# 03_-_28PINS_SCHEMATIC.net
KiCad netlist of a schematic drawn in Altium Designer
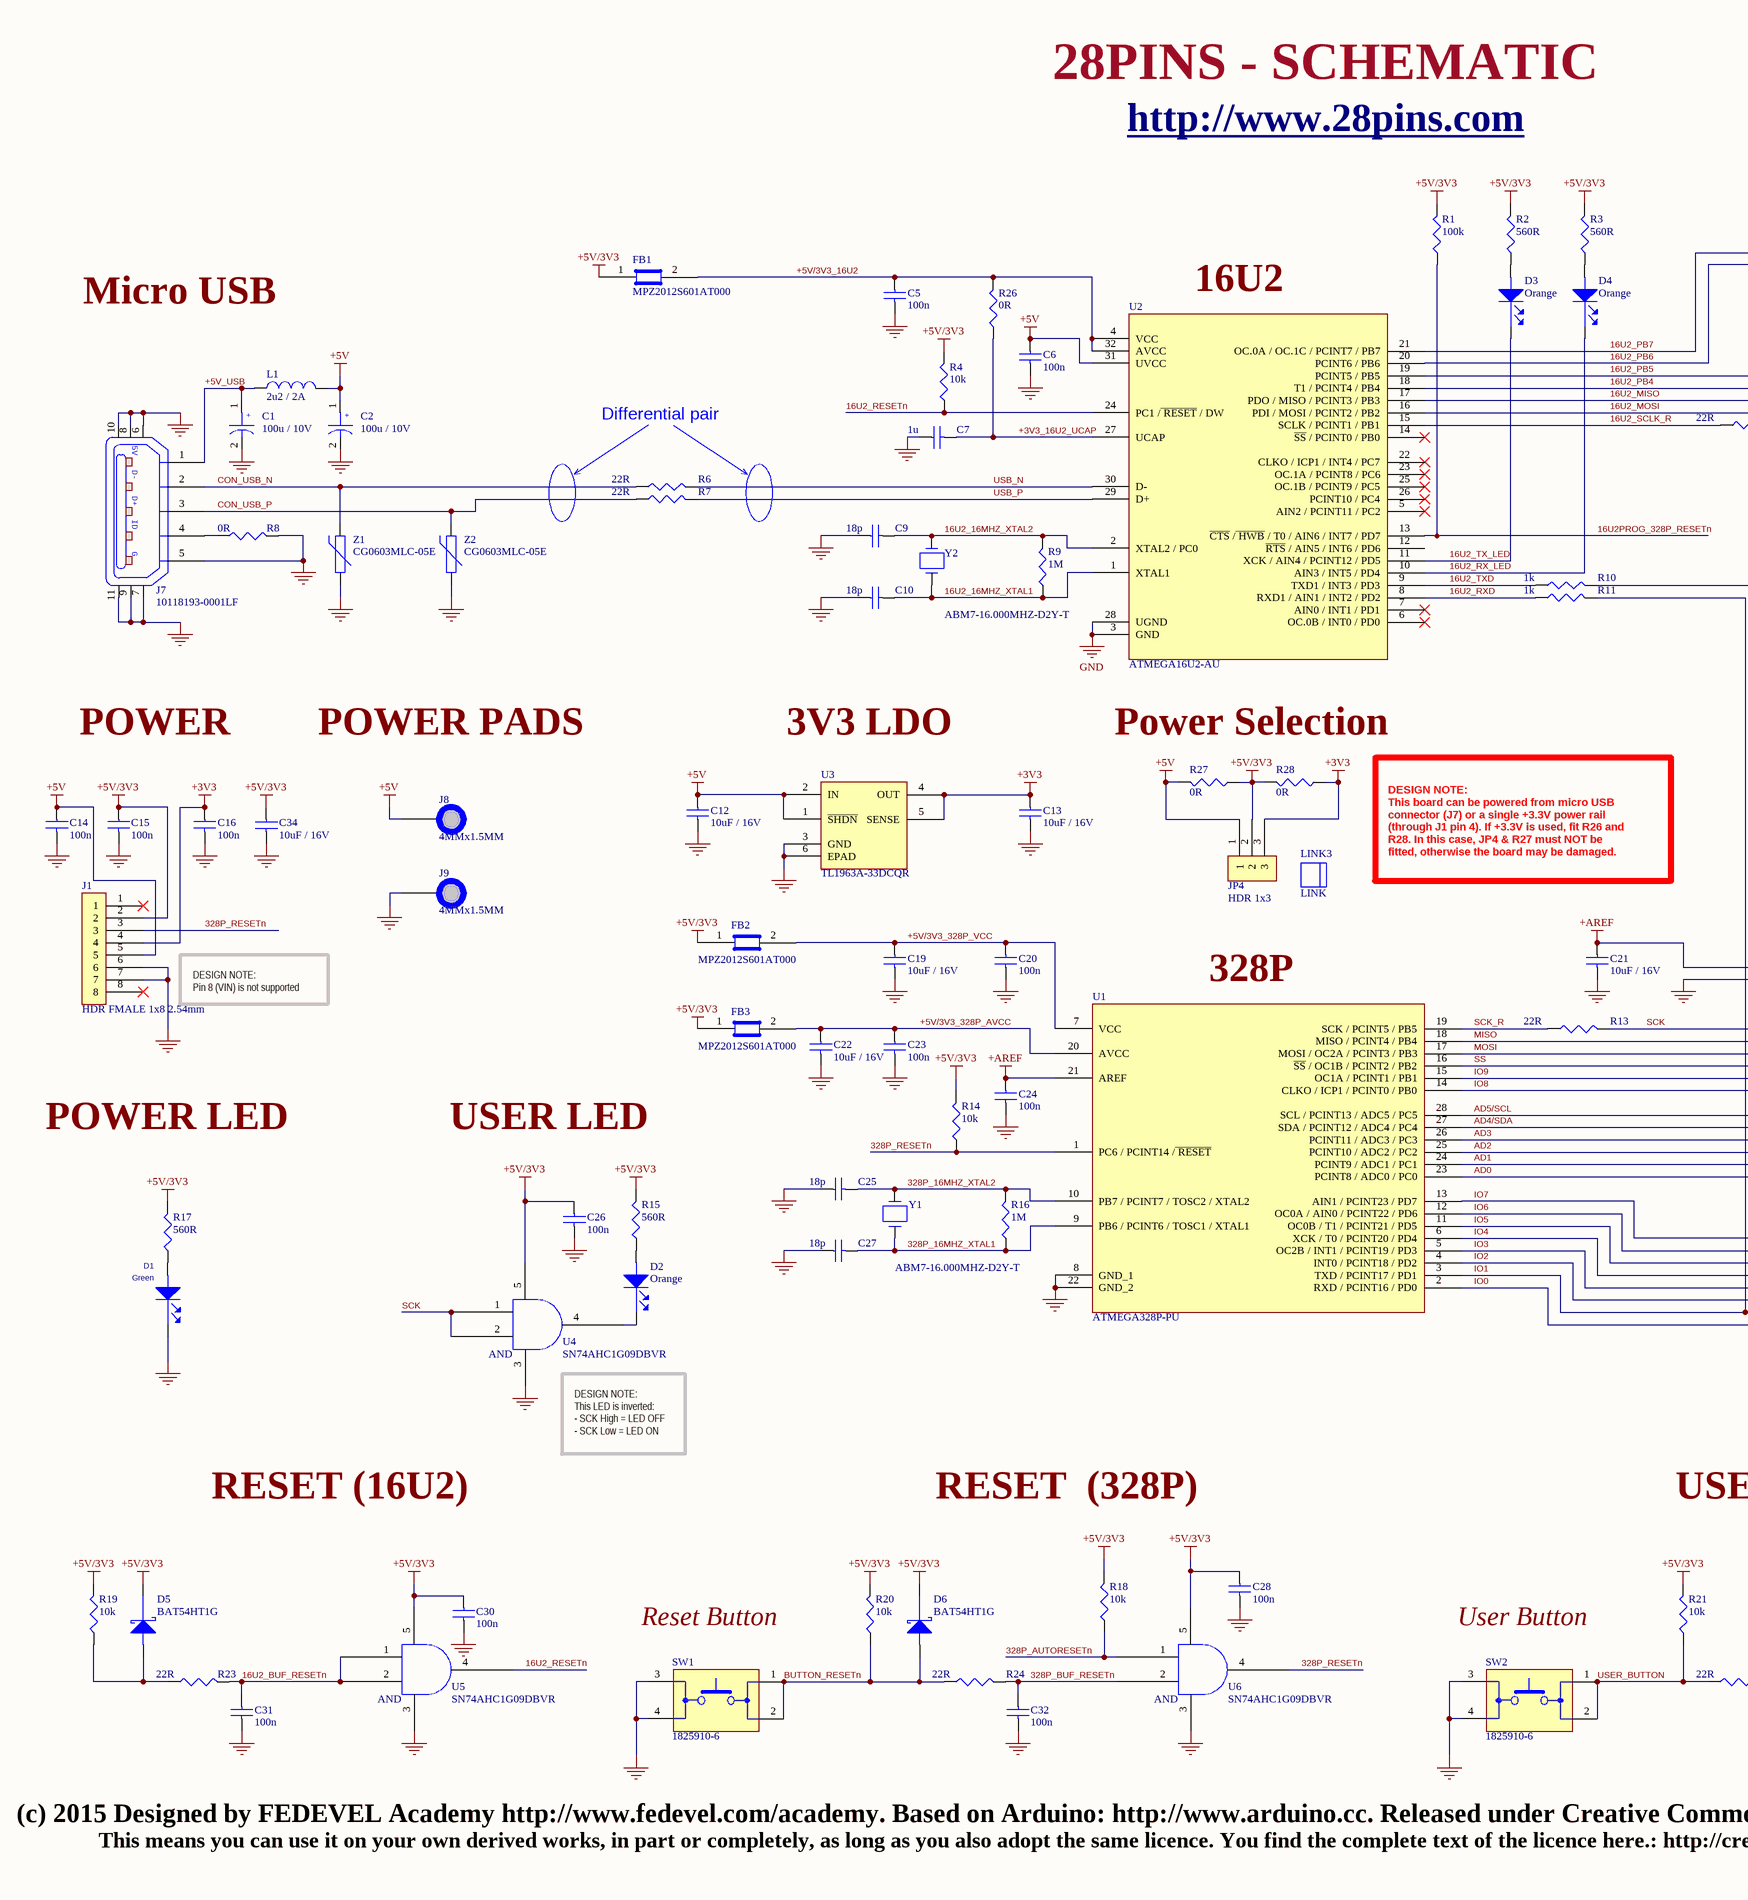
[diagram p0: [03] - 28PINS SCHEMATIC.SchDoc, left]
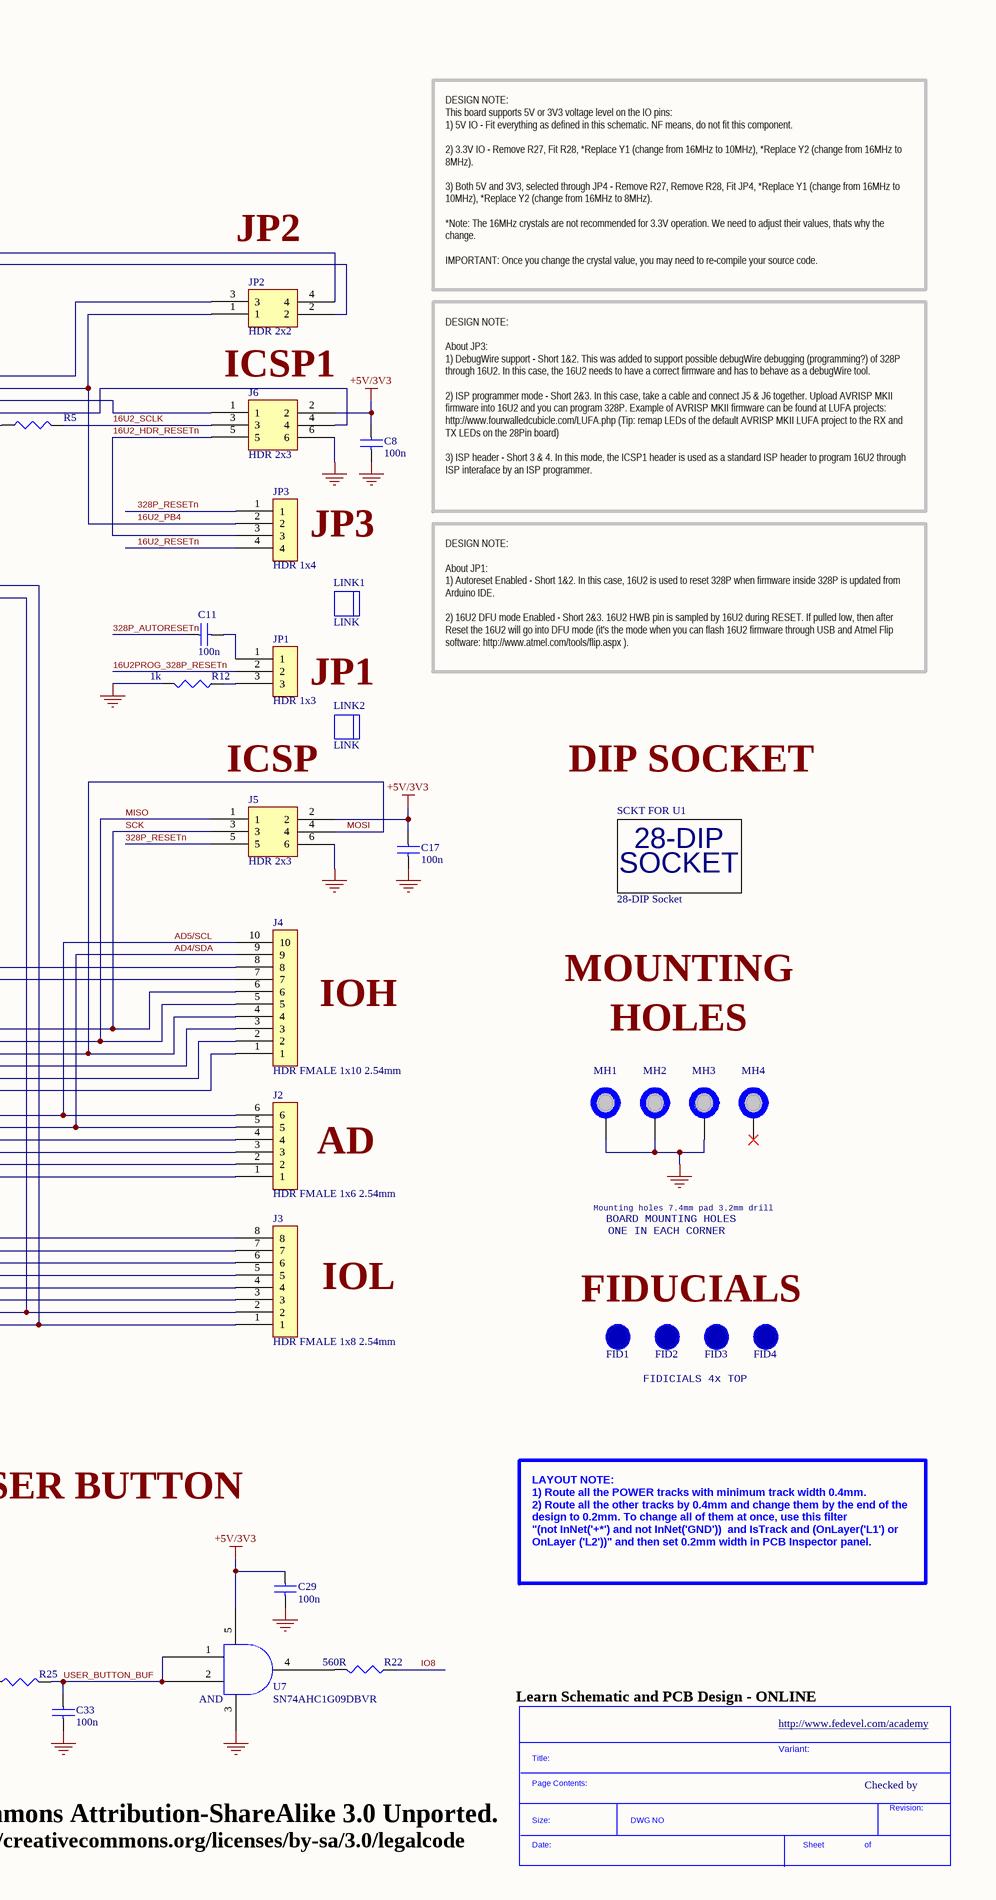
[diagram p1: [03] - 28PINS SCHEMATIC.SchDoc, right]

(export (version "E")
  (design (tool "Eeschema 10.0.6"))
  (components
    (comp (ref "C1")
      (value "100u / 10V")
      (footprint "C_ALU_C_SIZE")
      (description "CAP ALUM 100UF 10V 20% SMD")
      (fields
        (field (name "MANUFACTURER") "Panasonic Electronic Components")
        (field (name "MANUFACTURER PART NUMBER") "EEE-1AA101WR")
        (field (name ".CREATOR") "MM")
        (field (name ".CHECKED PCB") "RF")
        (field (name ".CHECKED SCH") "RF")
      )
      (libsource (lib "Integrated_Library_FEDEVEL_APR_2015") (part "EEE-1AA101WR"))
    )
    (comp (ref "C2")
      (value "100u / 10V")
      (footprint "C_ALU_C_SIZE")
      (description "CAP ALUM 100UF 10V 20% SMD")
      (fields
        (field (name "MANUFACTURER") "Panasonic Electronic Components")
        (field (name "MANUFACTURER PART NUMBER") "EEE-1AA101WR")
        (field (name ".CREATOR") "MM")
        (field (name ".CHECKED PCB") "RF")
        (field (name ".CHECKED SCH") "RF")
      )
      (libsource (lib "Integrated_Library_FEDEVEL_APR_2015") (part "EEE-1AA101WR"))
    )
    (comp (ref "C5")
      (value "100n")
      (footprint "C0805")
      (description "CAP CER 0.1UF 50V 10% X7R 0805")
      (fields
        (field (name "MANUFACTURER") "TDK Corporation")
        (field (name "MANUFACTURER PART NUMBER") "C2012X7R1H104K085AA")
        (field (name ".CREATOR") "MM")
        (field (name ".CHECKED PCB") "RF")
        (field (name ".CHECKED SCH") "RF")
      )
      (libsource (lib "Integrated_Library_FEDEVEL_APR_2015") (part "C2012X7R1H104K085AA"))
    )
    (comp (ref "C6")
      (value "100n")
      (footprint "C0805")
      (description "CAP CER 0.1UF 50V 10% X7R 0805")
      (fields
        (field (name "MANUFACTURER") "TDK Corporation")
        (field (name "MANUFACTURER PART NUMBER") "C2012X7R1H104K085AA")
        (field (name ".CREATOR") "MM")
        (field (name ".CHECKED PCB") "RF")
        (field (name ".CHECKED SCH") "RF")
      )
      (libsource (lib "Integrated_Library_FEDEVEL_APR_2015") (part "C2012X7R1H104K085AA"))
    )
    (comp (ref "C7")
      (value "1u")
      (footprint "C0805")
      (description "CAP CER 1UF 25V 10% X5R 0805")
      (fields
        (field (name "MANUFACTURER") "TDK Corporation")
        (field (name "MANUFACTURER PART NUMBER") "C2012X5R1E105K125AA")
        (field (name ".CREATOR") "MM")
        (field (name ".CHECKED PCB") "RF")
        (field (name ".CHECKED SCH") "RF")
      )
      (libsource (lib "Integrated_Library_FEDEVEL_APR_2015") (part "C2012X5R1E105K125AA"))
    )
    (comp (ref "C8")
      (value "100n")
      (footprint "C0805")
      (description "CAP CER 0.1UF 50V 10% X7R 0805")
      (fields
        (field (name "MANUFACTURER") "TDK Corporation")
        (field (name "MANUFACTURER PART NUMBER") "C2012X7R1H104K085AA")
        (field (name ".CREATOR") "MM")
        (field (name ".CHECKED PCB") "RF")
        (field (name ".CHECKED SCH") "RF")
      )
      (libsource (lib "Integrated_Library_FEDEVEL_APR_2015") (part "C2012X7R1H104K085AA"))
    )
    (comp (ref "C9")
      (value "18p")
      (footprint "C0805")
      (description "CAP CER 18PF 50V 5% NP0 0805")
      (fields
        (field (name "MANUFACTURER") "Kemet")
        (field (name "MANUFACTURER PART NUMBER") "C0805C180J5GACTU")
        (field (name ".CREATOR") "MM")
        (field (name ".CHECKED PCB") "RF")
        (field (name ".CHECKED SCH") "RF")
      )
      (libsource (lib "Integrated_Library_FEDEVEL_APR_2015") (part "C0805C180J5GACTU"))
    )
    (comp (ref "C10")
      (value "18p")
      (footprint "C0805")
      (description "CAP CER 18PF 50V 5% NP0 0805")
      (fields
        (field (name "MANUFACTURER") "Kemet")
        (field (name "MANUFACTURER PART NUMBER") "C0805C180J5GACTU")
        (field (name ".CREATOR") "MM")
        (field (name ".CHECKED PCB") "RF")
        (field (name ".CHECKED SCH") "RF")
      )
      (libsource (lib "Integrated_Library_FEDEVEL_APR_2015") (part "C0805C180J5GACTU"))
    )
    (comp (ref "C11")
      (value "100n")
      (footprint "C0805")
      (description "CAP CER 0.1UF 50V 10% X7R 0805")
      (fields
        (field (name "MANUFACTURER") "TDK Corporation")
        (field (name "MANUFACTURER PART NUMBER") "C2012X7R1H104K085AA")
        (field (name ".CREATOR") "MM")
        (field (name ".CHECKED PCB") "RF")
        (field (name ".CHECKED SCH") "RF")
      )
      (libsource (lib "Integrated_Library_FEDEVEL_APR_2015") (part "C2012X7R1H104K085AA"))
    )
    (comp (ref "C12")
      (value "10uF / 16V")
      (footprint "C0805")
      (description "CAP CER 10UF 16V 20% X5R 0805")
      (fields
        (field (name "MANUFACTURER") "TDK Corporation")
        (field (name "MANUFACTURER PART NUMBER") "C2012X5R1C106M/1.25")
      )
      (libsource (lib "Integrated_Library_FEDEVEL_APR_2015") (part "C2012X5R1C106M"))
    )
    (comp (ref "C13")
      (value "10uF / 16V")
      (footprint "C0805")
      (description "CAP CER 10UF 16V 20% X5R 0805")
      (fields
        (field (name "MANUFACTURER") "TDK Corporation")
        (field (name "MANUFACTURER PART NUMBER") "C2012X5R1C106M/1.25")
      )
      (libsource (lib "Integrated_Library_FEDEVEL_APR_2015") (part "C2012X5R1C106M"))
    )
    (comp (ref "C14")
      (value "100n")
      (footprint "C0805")
      (description "CAP CER 0.1UF 50V 10% X7R 0805")
      (fields
        (field (name "MANUFACTURER") "TDK Corporation")
        (field (name "MANUFACTURER PART NUMBER") "C2012X7R1H104K085AA")
        (field (name ".CREATOR") "MM")
        (field (name ".CHECKED PCB") "RF")
        (field (name ".CHECKED SCH") "RF")
      )
      (libsource (lib "Integrated_Library_FEDEVEL_APR_2015") (part "C2012X7R1H104K085AA"))
    )
    (comp (ref "C15")
      (value "100n")
      (footprint "C0805")
      (description "CAP CER 0.1UF 50V 10% X7R 0805")
      (fields
        (field (name "MANUFACTURER") "TDK Corporation")
        (field (name "MANUFACTURER PART NUMBER") "C2012X7R1H104K085AA")
        (field (name ".CREATOR") "MM")
        (field (name ".CHECKED PCB") "RF")
        (field (name ".CHECKED SCH") "RF")
      )
      (libsource (lib "Integrated_Library_FEDEVEL_APR_2015") (part "C2012X7R1H104K085AA"))
    )
    (comp (ref "C16")
      (value "100n")
      (footprint "C0805")
      (description "CAP CER 0.1UF 50V 10% X7R 0805")
      (fields
        (field (name "MANUFACTURER") "TDK Corporation")
        (field (name "MANUFACTURER PART NUMBER") "C2012X7R1H104K085AA")
        (field (name ".CREATOR") "MM")
        (field (name ".CHECKED PCB") "RF")
        (field (name ".CHECKED SCH") "RF")
      )
      (libsource (lib "Integrated_Library_FEDEVEL_APR_2015") (part "C2012X7R1H104K085AA"))
    )
    (comp (ref "C17")
      (value "100n")
      (footprint "C0805")
      (description "CAP CER 0.1UF 50V 10% X7R 0805")
      (fields
        (field (name "MANUFACTURER") "TDK Corporation")
        (field (name "MANUFACTURER PART NUMBER") "C2012X7R1H104K085AA")
        (field (name ".CREATOR") "MM")
        (field (name ".CHECKED PCB") "RF")
        (field (name ".CHECKED SCH") "RF")
      )
      (libsource (lib "Integrated_Library_FEDEVEL_APR_2015") (part "C2012X7R1H104K085AA"))
    )
    (comp (ref "C19")
      (value "10uF / 16V")
      (footprint "C0805")
      (description "CAP CER 10UF 16V 20% X5R 0805")
      (fields
        (field (name "MANUFACTURER") "TDK Corporation")
        (field (name "MANUFACTURER PART NUMBER") "C2012X5R1C106M/1.25")
      )
      (libsource (lib "Integrated_Library_FEDEVEL_APR_2015") (part "C2012X5R1C106M"))
    )
    (comp (ref "C20")
      (value "100n")
      (footprint "C0805")
      (description "CAP CER 0.1UF 50V 10% X7R 0805")
      (fields
        (field (name "MANUFACTURER") "TDK Corporation")
        (field (name "MANUFACTURER PART NUMBER") "C2012X7R1H104K085AA")
        (field (name ".CREATOR") "MM")
        (field (name ".CHECKED PCB") "RF")
        (field (name ".CHECKED SCH") "RF")
      )
      (libsource (lib "Integrated_Library_FEDEVEL_APR_2015") (part "C2012X7R1H104K085AA"))
    )
    (comp (ref "C21")
      (value "10uF / 16V")
      (footprint "C0805")
      (description "CAP CER 10UF 16V 20% X5R 0805")
      (fields
        (field (name "MANUFACTURER") "TDK Corporation")
        (field (name "MANUFACTURER PART NUMBER") "C2012X5R1C106M/1.25")
      )
      (libsource (lib "Integrated_Library_FEDEVEL_APR_2015") (part "C2012X5R1C106M"))
    )
    (comp (ref "C22")
      (value "10uF / 16V")
      (footprint "C0805")
      (description "CAP CER 10UF 16V 20% X5R 0805")
      (fields
        (field (name "MANUFACTURER") "TDK Corporation")
        (field (name "MANUFACTURER PART NUMBER") "C2012X5R1C106M/1.25")
      )
      (libsource (lib "Integrated_Library_FEDEVEL_APR_2015") (part "C2012X5R1C106M"))
    )
    (comp (ref "C23")
      (value "100n")
      (footprint "C0805")
      (description "CAP CER 0.1UF 50V 10% X7R 0805")
      (fields
        (field (name "MANUFACTURER") "TDK Corporation")
        (field (name "MANUFACTURER PART NUMBER") "C2012X7R1H104K085AA")
        (field (name ".CREATOR") "MM")
        (field (name ".CHECKED PCB") "RF")
        (field (name ".CHECKED SCH") "RF")
      )
      (libsource (lib "Integrated_Library_FEDEVEL_APR_2015") (part "C2012X7R1H104K085AA"))
    )
    (comp (ref "C24")
      (value "100n")
      (footprint "C0805")
      (description "CAP CER 0.1UF 50V 10% X7R 0805")
      (fields
        (field (name "MANUFACTURER") "TDK Corporation")
        (field (name "MANUFACTURER PART NUMBER") "C2012X7R1H104K085AA")
        (field (name ".CREATOR") "MM")
        (field (name ".CHECKED PCB") "RF")
        (field (name ".CHECKED SCH") "RF")
      )
      (libsource (lib "Integrated_Library_FEDEVEL_APR_2015") (part "C2012X7R1H104K085AA"))
    )
    (comp (ref "C25")
      (value "18p")
      (footprint "C0805")
      (description "CAP CER 18PF 50V 5% NP0 0805")
      (fields
        (field (name "MANUFACTURER") "Kemet")
        (field (name "MANUFACTURER PART NUMBER") "C0805C180J5GACTU")
        (field (name ".CREATOR") "MM")
        (field (name ".CHECKED PCB") "RF")
        (field (name ".CHECKED SCH") "RF")
      )
      (libsource (lib "Integrated_Library_FEDEVEL_APR_2015") (part "C0805C180J5GACTU"))
    )
    (comp (ref "C26")
      (value "100n")
      (footprint "C0805")
      (description "CAP CER 0.1UF 50V 10% X7R 0805")
      (fields
        (field (name "MANUFACTURER") "TDK Corporation")
        (field (name "MANUFACTURER PART NUMBER") "C2012X7R1H104K085AA")
        (field (name ".CREATOR") "MM")
        (field (name ".CHECKED PCB") "RF")
        (field (name ".CHECKED SCH") "RF")
      )
      (libsource (lib "Integrated_Library_FEDEVEL_APR_2015") (part "C2012X7R1H104K085AA"))
    )
    (comp (ref "C27")
      (value "18p")
      (footprint "C0805")
      (description "CAP CER 18PF 50V 5% NP0 0805")
      (fields
        (field (name "MANUFACTURER") "Kemet")
        (field (name "MANUFACTURER PART NUMBER") "C0805C180J5GACTU")
        (field (name ".CREATOR") "MM")
        (field (name ".CHECKED PCB") "RF")
        (field (name ".CHECKED SCH") "RF")
      )
      (libsource (lib "Integrated_Library_FEDEVEL_APR_2015") (part "C0805C180J5GACTU"))
    )
    (comp (ref "C28")
      (value "100n")
      (footprint "C0805")
      (description "CAP CER 0.1UF 50V 10% X7R 0805")
      (fields
        (field (name "MANUFACTURER") "TDK Corporation")
        (field (name "MANUFACTURER PART NUMBER") "C2012X7R1H104K085AA")
        (field (name ".CREATOR") "MM")
        (field (name ".CHECKED PCB") "RF")
        (field (name ".CHECKED SCH") "RF")
      )
      (libsource (lib "Integrated_Library_FEDEVEL_APR_2015") (part "C2012X7R1H104K085AA"))
    )
    (comp (ref "C29")
      (value "100n")
      (footprint "C0805")
      (description "CAP CER 0.1UF 50V 10% X7R 0805")
      (fields
        (field (name "MANUFACTURER") "TDK Corporation")
        (field (name "MANUFACTURER PART NUMBER") "C2012X7R1H104K085AA")
        (field (name ".CREATOR") "MM")
        (field (name ".CHECKED PCB") "RF")
        (field (name ".CHECKED SCH") "RF")
      )
      (libsource (lib "Integrated_Library_FEDEVEL_APR_2015") (part "C2012X7R1H104K085AA"))
    )
    (comp (ref "C30")
      (value "100n")
      (footprint "C0805")
      (description "CAP CER 0.1UF 50V 10% X7R 0805")
      (fields
        (field (name "MANUFACTURER") "TDK Corporation")
        (field (name "MANUFACTURER PART NUMBER") "C2012X7R1H104K085AA")
        (field (name ".CREATOR") "MM")
        (field (name ".CHECKED PCB") "RF")
        (field (name ".CHECKED SCH") "RF")
      )
      (libsource (lib "Integrated_Library_FEDEVEL_APR_2015") (part "C2012X7R1H104K085AA"))
    )
    (comp (ref "C31")
      (value "100n")
      (footprint "C0805")
      (description "CAP CER 0.1UF 50V 10% X7R 0805")
      (fields
        (field (name "MANUFACTURER") "TDK Corporation")
        (field (name "MANUFACTURER PART NUMBER") "C2012X7R1H104K085AA")
        (field (name ".CREATOR") "MM")
        (field (name ".CHECKED PCB") "RF")
        (field (name ".CHECKED SCH") "RF")
      )
      (libsource (lib "Integrated_Library_FEDEVEL_APR_2015") (part "C2012X7R1H104K085AA"))
    )
    (comp (ref "C32")
      (value "100n")
      (footprint "C0805")
      (description "CAP CER 0.1UF 50V 10% X7R 0805")
      (fields
        (field (name "MANUFACTURER") "TDK Corporation")
        (field (name "MANUFACTURER PART NUMBER") "C2012X7R1H104K085AA")
        (field (name ".CREATOR") "MM")
        (field (name ".CHECKED PCB") "RF")
        (field (name ".CHECKED SCH") "RF")
      )
      (libsource (lib "Integrated_Library_FEDEVEL_APR_2015") (part "C2012X7R1H104K085AA"))
    )
    (comp (ref "C33")
      (value "100n")
      (footprint "C0805")
      (description "CAP CER 0.1UF 50V 10% X7R 0805")
      (fields
        (field (name "MANUFACTURER") "TDK Corporation")
        (field (name "MANUFACTURER PART NUMBER") "C2012X7R1H104K085AA")
        (field (name ".CREATOR") "MM")
        (field (name ".CHECKED PCB") "RF")
        (field (name ".CHECKED SCH") "RF")
      )
      (libsource (lib "Integrated_Library_FEDEVEL_APR_2015") (part "C2012X7R1H104K085AA"))
    )
    (comp (ref "C34")
      (value "10uF / 16V")
      (footprint "C0805")
      (description "CAP CER 10UF 16V 20% X5R 0805")
      (fields
        (field (name "MANUFACTURER") "TDK Corporation")
        (field (name "MANUFACTURER PART NUMBER") "C2012X5R1C106M/1.25")
      )
      (libsource (lib "Integrated_Library_FEDEVEL_APR_2015") (part "C2012X5R1C106M"))
    )
    (comp (ref "D1")
      (value "Green")
      (footprint "LED_0603")
      (description "LED SMARTLED GREEN 570NM 0603")
      (fields
        (field (name "MANUFACTURER") "OSRAM Opto Semiconductors Inc")
        (field (name "MANUFACTURER PART NUMBER") "LG L29K-G2J1-24-Z")
      )
      (libsource (lib "Integrated_Library_FEDEVEL_APR_2015") (part "LG L29K-G2J1-24-Z"))
    )
    (comp (ref "D2")
      (value "Orange")
      (footprint "LED_0603")
      (description "LED SMARTLED ORANGE 606NM 0603")
      (fields
        (field (name "MANUFACTURER") "OSRAM Opto Semiconductors Inc")
        (field (name "MANUFACTURER PART NUMBER") "LO L29K-H2K1-24-Z")
      )
      (libsource (lib "Integrated_Library_FEDEVEL_APR_2015") (part "LO L29K-H2K1-24-Z"))
    )
    (comp (ref "D3")
      (value "Orange")
      (footprint "LED_0603")
      (description "LED SMARTLED ORANGE 606NM 0603")
      (fields
        (field (name "MANUFACTURER") "OSRAM Opto Semiconductors Inc")
        (field (name "MANUFACTURER PART NUMBER") "LO L29K-H2K1-24-Z")
      )
      (libsource (lib "Integrated_Library_FEDEVEL_APR_2015") (part "LO L29K-H2K1-24-Z"))
    )
    (comp (ref "D4")
      (value "Orange")
      (footprint "LED_0603")
      (description "LED SMARTLED ORANGE 606NM 0603")
      (fields
        (field (name "MANUFACTURER") "OSRAM Opto Semiconductors Inc")
        (field (name "MANUFACTURER PART NUMBER") "LO L29K-H2K1-24-Z")
      )
      (libsource (lib "Integrated_Library_FEDEVEL_APR_2015") (part "LO L29K-H2K1-24-Z"))
    )
    (comp (ref "D5")
      (value "BAT54HT1G")
      (footprint "SOD323")
      (description "DIODE SCHOTTKY 30V 0.2A SOD323")
      (fields (field (name "MANUFACTURER") "Fairchild Semiconductor") (field (name ".CREATOR") "MM"))
      (libsource (lib "Integrated_Library_FEDEVEL_APR_2015") (part "BAT54HT1G"))
    )
    (comp (ref "D6")
      (value "BAT54HT1G")
      (footprint "SOD323")
      (description "DIODE SCHOTTKY 30V 0.2A SOD323")
      (fields (field (name "MANUFACTURER") "Fairchild Semiconductor") (field (name ".CREATOR") "MM"))
      (libsource (lib "Integrated_Library_FEDEVEL_APR_2015") (part "BAT54HT1G"))
    )
    (comp (ref "FB1")
      (value "MPZ2012S601AT000")
      (footprint "C0805")
      (description "FERRITE CHIP BEAD 600 OHM SMD")
      (fields
        (field (name "MANUFACTURER") "TDK Corporation")
        (field (name ".CREATOR") "MM")
        (field (name ".CHECKED PCB") "RF")
        (field (name ".CHECKED SCH") "RF")
      )
      (libsource (lib "Integrated_Library_FEDEVEL_APR_2015") (part "MPZ2012S601AT000"))
    )
    (comp (ref "FB2")
      (value "MPZ2012S601AT000")
      (footprint "C0805")
      (description "FERRITE CHIP BEAD 600 OHM SMD")
      (fields
        (field (name "MANUFACTURER") "TDK Corporation")
        (field (name ".CREATOR") "MM")
        (field (name ".CHECKED PCB") "RF")
        (field (name ".CHECKED SCH") "RF")
      )
      (libsource (lib "Integrated_Library_FEDEVEL_APR_2015") (part "MPZ2012S601AT000"))
    )
    (comp (ref "FB3")
      (value "MPZ2012S601AT000")
      (footprint "C0805")
      (description "FERRITE CHIP BEAD 600 OHM SMD")
      (fields
        (field (name "MANUFACTURER") "TDK Corporation")
        (field (name ".CREATOR") "MM")
        (field (name ".CHECKED PCB") "RF")
        (field (name ".CHECKED SCH") "RF")
      )
      (libsource (lib "Integrated_Library_FEDEVEL_APR_2015") (part "MPZ2012S601AT000"))
    )
    (comp (ref "FID1")
      (value "FID_1MMC")
      (footprint "FID_40X120D")
      (description "Fiducial 40mil Diameter, 120mil Mask")
      (libsource (lib "Integrated_Library_FEDEVEL_APR_2015") (part "FID_1MMC"))
    )
    (comp (ref "FID2")
      (value "FID_1MMC")
      (footprint "FID_40X120D")
      (description "Fiducial 40mil Diameter, 120mil Mask")
      (libsource (lib "Integrated_Library_FEDEVEL_APR_2015") (part "FID_1MMC"))
    )
    (comp (ref "FID3")
      (value "FID_1MMC")
      (footprint "FID_40X120D")
      (description "Fiducial 40mil Diameter, 120mil Mask")
      (libsource (lib "Integrated_Library_FEDEVEL_APR_2015") (part "FID_1MMC"))
    )
    (comp (ref "FID4")
      (value "FID_1MMC")
      (footprint "FID_40X120D")
      (description "Fiducial 40mil Diameter, 120mil Mask")
      (libsource (lib "Integrated_Library_FEDEVEL_APR_2015") (part "FID_1MMC"))
    )
    (comp (ref "J1")
      (value "HDR FMALE 1x8 2.54mm")
      (footprint "Hdr_Female_1x8_2.54mm")
      (description "08-WAY SIL VERT SOCKET L/FREE")
      (fields
        (field (name "MANUFACTURER") "Harwin Inc")
        (field (name "MANUFACTURER PART NUMBER") "M20-7820842")
        (field (name ".CREATOR") "MM")
        (field (name ".CHECKED PCB") "RF")
        (field (name ".CHECKED SCH") "RF")
      )
      (libsource (lib "") (part "M20-7820842_1"))
    )
    (comp (ref "J2")
      (value "HDR FMALE 1x6 2.54mm")
      (footprint "Hdr_Female_1x6_2.54mm")
      (description "06-WAY SIL VERT SOCKET L/FREE")
      (fields
        (field (name "MANUFACTURER") "Harwin Inc")
        (field (name "MANUFACTURER PART NUMBER") "M20-7820646")
        (field (name ".CHECKED PCB") "MM")
        (field (name ".CHECKED SCH") "MM")
        (field (name ".CREATOR") "MM")
      )
      (libsource (lib "Integrated_Library_FEDEVEL_APR_2015") (part "M20-7820646"))
    )
    (comp (ref "J3")
      (value "HDR FMALE 1x8 2.54mm")
      (footprint "Hdr_Female_1x8_2.54mm")
      (description "08-WAY SIL VERT SOCKET L/FREE")
      (fields
        (field (name "MANUFACTURER") "Harwin Inc")
        (field (name "MANUFACTURER PART NUMBER") "M20-7820842")
        (field (name ".CREATOR") "MM")
        (field (name ".CHECKED PCB") "RF")
        (field (name ".CHECKED SCH") "RF")
      )
      (libsource (lib "Integrated_Library_FEDEVEL_APR_2015") (part "M20-7820842"))
    )
    (comp (ref "J4")
      (value "HDR FMALE 1x10 2.54mm")
      (footprint "Hdr_Female_1x10_2.54mm")
      (description "10-WAY SIL VERT SOCKET L/FREE")
      (fields
        (field (name "MANUFACTURER") "Harwin Inc")
        (field (name "MANUFACTURER PART NUMBER") "M20-7821046")
        (field (name ".CREATOR") "MM")
        (field (name ".CHECKED PCB") "RF")
        (field (name ".CHECKED SCH") "RF")
      )
      (libsource (lib "Integrated_Library_FEDEVEL_APR_2015") (part "M20-7821046"))
    )
    (comp (ref "J5")
      (value "HDR 2x3")
      (footprint "HDR_2x3_2.54MM")
      (description "CONN HEADER 6POS .100 STR 30AU")
      (fields
        (field (name "MANUFACTURER") "FCI")
        (field (name "MANUFACTURER PART NUMBER") "67997-106HLF")
        (field (name ".CREATOR") "MM")
        (field (name ".CHECKED PCB") "RF")
        (field (name ".CHECKED SCH") "RF")
      )
      (libsource (lib "Integrated_Library_FEDEVEL_APR_2015") (part "67997-106HLF"))
    )
    (comp (ref "J6")
      (value "HDR 2x3")
      (footprint "HDR_2x3_2.54MM")
      (description "CONN HEADER 6POS .100 STR 30AU")
      (fields
        (field (name "MANUFACTURER") "FCI")
        (field (name "MANUFACTURER PART NUMBER") "67997-106HLF")
        (field (name ".CREATOR") "MM")
        (field (name ".CHECKED PCB") "RF")
        (field (name ".CHECKED SCH") "RF")
      )
      (libsource (lib "Integrated_Library_FEDEVEL_APR_2015") (part "67997-106HLF"))
    )
    (comp (ref "J7")
      (value "10118193-0001LF")
      (footprint "10118193")
      (description "CONN USB MICRO B RECPT SMT R/A")
      (fields
        (field (name "MANUFACTURER") "FCI")
        (field (name ".CREATOR") "MM")
        (field (name ".CHECKED PCB") "RF")
        (field (name ".CHECKED SCH") "MM")
      )
      (libsource (lib "Integrated_Library_FEDEVEL_APR_2015") (part "10118193-0001LF"))
    )
    (comp (ref "J8")
      (value "4MMx1.5MM")
      (footprint "PAD_WITH_HOLE_4MMx1.5MM")
      (description "Pad with a hole 4mm x 1.5mm")
      (libsource (lib "Integrated_Library_FEDEVEL_APR_2015") (part "PAD_WITH_HOLE_4MMx1.5MM"))
    )
    (comp (ref "J9")
      (value "4MMx1.5MM")
      (footprint "PAD_WITH_HOLE_4MMx1.5MM")
      (description "Pad with a hole 4mm x 1.5mm")
      (libsource (lib "Integrated_Library_FEDEVEL_APR_2015") (part "PAD_WITH_HOLE_4MMx1.5MM"))
    )
    (comp (ref "JP1")
      (value "HDR 1x3")
      (footprint "Hdr_1x3_2.54mm")
      (description "BERGSTIK II .100\" SR STRAIGHT")
      (fields
        (field (name "MANUFACTURER") "FCI")
        (field (name "MANUFACTURER PART NUMBER") "68000-103HLF")
        (field (name ".CREATOR") "MM")
      )
      (libsource (lib "") (part "68000-103HLF_1"))
    )
    (comp (ref "JP2")
      (value "HDR 2x2")
      (footprint "HDR_2x2_2.54MM")
      (description "CONN HEADER 4POS .100 STR 15AU")
      (fields
        (field (name "MANUFACTURER") "FCI")
        (field (name "MANUFACTURER PART NUMBER") "68602-204HLF")
        (field (name ".CREATOR") "MM")
        (field (name ".CHECKED PCB") "RF")
        (field (name ".CHECKED SCH") "RF")
      )
      (libsource (lib "Integrated_Library_FEDEVEL_APR_2015") (part "68602-204HLF"))
    )
    (comp (ref "JP3")
      (value "HDR 1x4")
      (footprint "HDR_1x4_2.54MM")
      (description "CONN HEADER 4POS .100 STR 15AU")
      (fields
        (field (name "MANUFACTURER") "FCI")
        (field (name "MANUFACTURER PART NUMBER") "68001-204HLF")
        (field (name ".CHECKED PCB") "RF")
        (field (name ".CHECKED SCH") "RF")
      )
      (libsource (lib "Integrated_Library_FEDEVEL_APR_2015") (part "68001-204HLF"))
    )
    (comp (ref "JP4")
      (value "HDR 1x3")
      (footprint "Hdr_1x3_2.54mm")
      (description "BERGSTIK II .100\" SR STRAIGHT")
      (fields
        (field (name "MANUFACTURER") "FCI")
        (field (name "MANUFACTURER PART NUMBER") "68000-103HLF")
        (field (name ".CREATOR") "MM")
      )
      (libsource (lib "Integrated_Library_FEDEVEL_APR_2015") (part "68000-103HLF"))
    )
    (comp (ref "L1")
      (value "2u2 / 2A")
      (footprint "C1210_IND")
      (description "FIXED IND 2.2UH 2A 80 MOHM SMD")
      (fields
        (field (name "MANUFACTURER") "Kemet")
        (field (name "MANUFACTURER PART NUMBER") "L1210R2R2MDWIT")
        (field (name ".CREATOR") "MM")
        (field (name ".CHECKED PCB") "RF")
        (field (name ".CHECKED SCH") "RF")
      )
      (libsource (lib "Integrated_Library_FEDEVEL_APR_2015") (part "L1210R2R2MDWIT"))
    )
    (comp (ref "LINK1")
      (value "LINK")
      (description "CONN JUMPER SHORTING .100\" GOLD")
      (fields
        (field (name "MANUFACTURER") "Sullins Connector Solutions")
        (field (name "MANUFACTURER PART NUMBER") "QPC02SXGN-RC")
      )
      (libsource (lib "Integrated_Library_FEDEVEL_APR_2015") (part "QPC02SXGN-RC"))
    )
    (comp (ref "LINK2")
      (value "LINK")
      (description "CONN JUMPER SHORTING .100\" GOLD")
      (fields
        (field (name "MANUFACTURER") "Sullins Connector Solutions")
        (field (name "MANUFACTURER PART NUMBER") "QPC02SXGN-RC")
      )
      (libsource (lib "Integrated_Library_FEDEVEL_APR_2015") (part "QPC02SXGN-RC"))
    )
    (comp (ref "LINK3")
      (value "LINK")
      (description "CONN JUMPER SHORTING .100\" GOLD")
      (fields
        (field (name "MANUFACTURER") "Sullins Connector Solutions")
        (field (name "MANUFACTURER PART NUMBER") "QPC02SXGN-RC")
      )
      (libsource (lib "Integrated_Library_FEDEVEL_APR_2015") (part "QPC02SXGN-RC"))
    )
    (comp (ref "MH1")
      (value "MH_7.4MMC_3.2MMD")
      (footprint "MH_7.4MMD_3.2MMD")
      (description "Mounting Hole 7.4mm Diameter, 3.2mm Drill")
      (fields (field (name ".CREATOR") "MM"))
      (libsource (lib "Integrated_Library_FEDEVEL_APR_2015") (part "MH_7.4MMC_3.2MMD"))
    )
    (comp (ref "MH2")
      (value "MH_7.4MMC_3.2MMD")
      (footprint "MH_7.4MMD_3.2MMD")
      (description "Mounting Hole 7.4mm Diameter, 3.2mm Drill")
      (fields (field (name ".CREATOR") "MM"))
      (libsource (lib "Integrated_Library_FEDEVEL_APR_2015") (part "MH_7.4MMC_3.2MMD"))
    )
    (comp (ref "MH3")
      (value "MH_7.4MMC_3.2MMD")
      (footprint "MH_7.4MMD_3.2MMD")
      (description "Mounting Hole 7.4mm Diameter, 3.2mm Drill")
      (fields (field (name ".CREATOR") "MM"))
      (libsource (lib "Integrated_Library_FEDEVEL_APR_2015") (part "MH_7.4MMC_3.2MMD"))
    )
    (comp (ref "MH4")
      (value "MH_7.4MMNC_3.2MMD")
      (footprint "MH_7.4MMD_3.2MMD_NON_COPPER_NPTH")
      (description "Mounting Hole 7.4mm Diameter (Non Copper), 3.2mm Drill NPTH")
      (libsource (lib "Integrated_Library_FEDEVEL_APR_2015") (part "MH_7.4MMNC_3.2MMD"))
    )
    (comp (ref "R1")
      (value "100k")
      (footprint "R0805")
      (description "RES SMD 100K OHM 1% 1/8W 0805")
      (fields
        (field (name "MANUFACTURER") "Yageo")
        (field (name "MANUFACTURER PART NUMBER") "RC0805FR-07100KL")
        (field (name ".CREATOR") "MM")
        (field (name ".CHECKED PCB") "RF")
        (field (name ".CHECKED SCH") "RF")
      )
      (libsource (lib "Integrated_Library_FEDEVEL_APR_2015") (part "RC0805FR-07100KL"))
    )
    (comp (ref "R2")
      (value "560R")
      (footprint "R0805")
      (description "RES SMD 560 OHM 1% 1/8W 0805")
      (fields
        (field (name "MANUFACTURER") "Yageo")
        (field (name "MANUFACTURER PART NUMBER") "RC0805FR-07560RL")
        (field (name ".CREATOR") "MM")
        (field (name ".CHECKED PCB") "RF")
        (field (name ".CHECKED SCH") "RF")
      )
      (libsource (lib "Integrated_Library_FEDEVEL_APR_2015") (part "RC0805FR-07560RL"))
    )
    (comp (ref "R3")
      (value "560R")
      (footprint "R0805")
      (description "RES SMD 560 OHM 1% 1/8W 0805")
      (fields
        (field (name "MANUFACTURER") "Yageo")
        (field (name "MANUFACTURER PART NUMBER") "RC0805FR-07560RL")
        (field (name ".CREATOR") "MM")
        (field (name ".CHECKED PCB") "RF")
        (field (name ".CHECKED SCH") "RF")
      )
      (libsource (lib "Integrated_Library_FEDEVEL_APR_2015") (part "RC0805FR-07560RL"))
    )
    (comp (ref "R4")
      (value "10k")
      (footprint "R0805")
      (description "RES SMD 10K OHM 1% 1/8W 0805")
      (fields
        (field (name "MANUFACTURER") "Yageo")
        (field (name "MANUFACTURER PART NUMBER") "RC0805FR-0710KL")
        (field (name ".CREATOR") "MM")
        (field (name ".CHECKED PCB") "RF")
        (field (name ".CHECKED SCH") "RF")
      )
      (libsource (lib "Integrated_Library_FEDEVEL_APR_2015") (part "RC0805FR-0710KL"))
    )
    (comp (ref "R5")
      (value "22R")
      (footprint "R0805")
      (description "RES SMD 22 OHM 1% 1/8W 0805")
      (fields
        (field (name "MANUFACTURER") "Yageo")
        (field (name "MANUFACTURER PART NUMBER") "RC0805FR-0722RL")
        (field (name ".CREATOR") "MM")
        (field (name ".CHECKED PCB") "RF")
        (field (name ".CHECKED SCH") "RF")
      )
      (libsource (lib "Integrated_Library_FEDEVEL_APR_2015") (part "RC0805FR-0722RL"))
    )
    (comp (ref "R6")
      (value "22R")
      (footprint "R0805")
      (description "RES SMD 22 OHM 1% 1/8W 0805")
      (fields
        (field (name "MANUFACTURER") "Yageo")
        (field (name "MANUFACTURER PART NUMBER") "RC0805FR-0722RL")
        (field (name ".CREATOR") "MM")
        (field (name ".CHECKED PCB") "RF")
        (field (name ".CHECKED SCH") "RF")
      )
      (libsource (lib "Integrated_Library_FEDEVEL_APR_2015") (part "RC0805FR-0722RL"))
    )
    (comp (ref "R7")
      (value "22R")
      (footprint "R0805")
      (description "RES SMD 22 OHM 1% 1/8W 0805")
      (fields
        (field (name "MANUFACTURER") "Yageo")
        (field (name "MANUFACTURER PART NUMBER") "RC0805FR-0722RL")
        (field (name ".CREATOR") "MM")
        (field (name ".CHECKED PCB") "RF")
        (field (name ".CHECKED SCH") "RF")
      )
      (libsource (lib "Integrated_Library_FEDEVEL_APR_2015") (part "RC0805FR-0722RL"))
    )
    (comp (ref "R8")
      (value "0R")
      (footprint "R0805")
      (description "RES 0.0 OHM 1/8W 0805 SMD")
      (fields
        (field (name "MANUFACTURER") "Yageo")
        (field (name "MANUFACTURER PART NUMBER") "RC0805JR-070RL")
        (field (name ".CHECKED PCB") "RF")
        (field (name ".CHECKED SCH") "RF")
      )
      (libsource (lib "Integrated_Library_FEDEVEL_APR_2015") (part "RC0805JR-070RL"))
    )
    (comp (ref "R9")
      (value "1M")
      (footprint "R0805")
      (description "RES SMD 1M OHM 1% 1/8W 0805")
      (fields
        (field (name "MANUFACTURER") "Yageo")
        (field (name "MANUFACTURER PART NUMBER") "RC0805FR-071ML")
        (field (name ".CREATOR") "MM")
        (field (name ".CHECKED PCB") "RF")
        (field (name ".CHECKED SCH") "RF")
      )
      (libsource (lib "Integrated_Library_FEDEVEL_APR_2015") (part "RC0805FR-071ML"))
    )
    (comp (ref "R10")
      (value "1k")
      (footprint "R0805")
      (description "RES SMD 1K OHM 1% 1/8W 0805")
      (fields
        (field (name "MANUFACTURER") "Yageo")
        (field (name "MANUFACTURER PART NUMBER") "RC0805FR-071KL")
        (field (name ".CREATOR") "MM")
        (field (name ".CHECKED PCB") "RF")
        (field (name ".CHECKED SCH") "RF")
      )
      (libsource (lib "Integrated_Library_FEDEVEL_APR_2015") (part "RC0805FR-071KL"))
    )
    (comp (ref "R11")
      (value "1k")
      (footprint "R0805")
      (description "RES SMD 1K OHM 1% 1/8W 0805")
      (fields
        (field (name "MANUFACTURER") "Yageo")
        (field (name "MANUFACTURER PART NUMBER") "RC0805FR-071KL")
        (field (name ".CREATOR") "MM")
        (field (name ".CHECKED PCB") "RF")
        (field (name ".CHECKED SCH") "RF")
      )
      (libsource (lib "Integrated_Library_FEDEVEL_APR_2015") (part "RC0805FR-071KL"))
    )
    (comp (ref "R12")
      (value "1k")
      (footprint "R0805")
      (description "RES SMD 1K OHM 1% 1/8W 0805")
      (fields
        (field (name "MANUFACTURER") "Yageo")
        (field (name "MANUFACTURER PART NUMBER") "RC0805FR-071KL")
        (field (name ".CREATOR") "MM")
        (field (name ".CHECKED PCB") "RF")
        (field (name ".CHECKED SCH") "RF")
      )
      (libsource (lib "Integrated_Library_FEDEVEL_APR_2015") (part "RC0805FR-071KL"))
    )
    (comp (ref "R13")
      (value "22R")
      (footprint "R0805")
      (description "RES SMD 22 OHM 1% 1/8W 0805")
      (fields
        (field (name "MANUFACTURER") "Yageo")
        (field (name "MANUFACTURER PART NUMBER") "RC0805FR-0722RL")
        (field (name ".CREATOR") "MM")
        (field (name ".CHECKED PCB") "RF")
        (field (name ".CHECKED SCH") "RF")
      )
      (libsource (lib "Integrated_Library_FEDEVEL_APR_2015") (part "RC0805FR-0722RL"))
    )
    (comp (ref "R14")
      (value "10k")
      (footprint "R0805")
      (description "RES SMD 10K OHM 1% 1/8W 0805")
      (fields
        (field (name "MANUFACTURER") "Yageo")
        (field (name "MANUFACTURER PART NUMBER") "RC0805FR-0710KL")
        (field (name ".CREATOR") "MM")
        (field (name ".CHECKED PCB") "RF")
        (field (name ".CHECKED SCH") "RF")
      )
      (libsource (lib "Integrated_Library_FEDEVEL_APR_2015") (part "RC0805FR-0710KL"))
    )
    (comp (ref "R15")
      (value "560R")
      (footprint "R0805")
      (description "RES SMD 560 OHM 1% 1/8W 0805")
      (fields
        (field (name "MANUFACTURER") "Yageo")
        (field (name "MANUFACTURER PART NUMBER") "RC0805FR-07560RL")
        (field (name ".CREATOR") "MM")
        (field (name ".CHECKED PCB") "RF")
        (field (name ".CHECKED SCH") "RF")
      )
      (libsource (lib "Integrated_Library_FEDEVEL_APR_2015") (part "RC0805FR-07560RL"))
    )
    (comp (ref "R16")
      (value "1M")
      (footprint "R0805")
      (description "RES SMD 1M OHM 1% 1/8W 0805")
      (fields
        (field (name "MANUFACTURER") "Yageo")
        (field (name "MANUFACTURER PART NUMBER") "RC0805FR-071ML")
        (field (name ".CREATOR") "MM")
        (field (name ".CHECKED PCB") "RF")
        (field (name ".CHECKED SCH") "RF")
      )
      (libsource (lib "Integrated_Library_FEDEVEL_APR_2015") (part "RC0805FR-071ML"))
    )
    (comp (ref "R17")
      (value "560R")
      (footprint "R0805")
      (description "RES SMD 560 OHM 1% 1/8W 0805")
      (fields
        (field (name "MANUFACTURER") "Yageo")
        (field (name "MANUFACTURER PART NUMBER") "RC0805FR-07560RL")
        (field (name ".CREATOR") "MM")
        (field (name ".CHECKED PCB") "RF")
        (field (name ".CHECKED SCH") "RF")
      )
      (libsource (lib "Integrated_Library_FEDEVEL_APR_2015") (part "RC0805FR-07560RL"))
    )
    (comp (ref "R18")
      (value "10k")
      (footprint "R0805")
      (description "RES SMD 10K OHM 1% 1/8W 0805")
      (fields
        (field (name "MANUFACTURER") "Yageo")
        (field (name "MANUFACTURER PART NUMBER") "RC0805FR-0710KL")
        (field (name ".CREATOR") "MM")
        (field (name ".CHECKED PCB") "RF")
        (field (name ".CHECKED SCH") "RF")
      )
      (libsource (lib "Integrated_Library_FEDEVEL_APR_2015") (part "RC0805FR-0710KL"))
    )
    (comp (ref "R19")
      (value "10k")
      (footprint "R0805")
      (description "RES SMD 10K OHM 1% 1/8W 0805")
      (fields
        (field (name "MANUFACTURER") "Yageo")
        (field (name "MANUFACTURER PART NUMBER") "RC0805FR-0710KL")
        (field (name ".CREATOR") "MM")
        (field (name ".CHECKED PCB") "RF")
        (field (name ".CHECKED SCH") "RF")
      )
      (libsource (lib "Integrated_Library_FEDEVEL_APR_2015") (part "RC0805FR-0710KL"))
    )
    (comp (ref "R20")
      (value "10k")
      (footprint "R0805")
      (description "RES SMD 10K OHM 1% 1/8W 0805")
      (fields
        (field (name "MANUFACTURER") "Yageo")
        (field (name "MANUFACTURER PART NUMBER") "RC0805FR-0710KL")
        (field (name ".CREATOR") "MM")
        (field (name ".CHECKED PCB") "RF")
        (field (name ".CHECKED SCH") "RF")
      )
      (libsource (lib "Integrated_Library_FEDEVEL_APR_2015") (part "RC0805FR-0710KL"))
    )
    (comp (ref "R21")
      (value "10k")
      (footprint "R0805")
      (description "RES SMD 10K OHM 1% 1/8W 0805")
      (fields
        (field (name "MANUFACTURER") "Yageo")
        (field (name "MANUFACTURER PART NUMBER") "RC0805FR-0710KL")
        (field (name ".CREATOR") "MM")
        (field (name ".CHECKED PCB") "RF")
        (field (name ".CHECKED SCH") "RF")
      )
      (libsource (lib "Integrated_Library_FEDEVEL_APR_2015") (part "RC0805FR-0710KL"))
    )
    (comp (ref "R22")
      (value "560R")
      (footprint "R0805")
      (description "RES SMD 560 OHM 1% 1/8W 0805")
      (fields
        (field (name "MANUFACTURER") "Yageo")
        (field (name "MANUFACTURER PART NUMBER") "RC0805FR-07560RL")
        (field (name ".CREATOR") "MM")
        (field (name ".CHECKED PCB") "RF")
        (field (name ".CHECKED SCH") "RF")
      )
      (libsource (lib "Integrated_Library_FEDEVEL_APR_2015") (part "RC0805FR-07560RL"))
    )
    (comp (ref "R23")
      (value "22R")
      (footprint "R0805")
      (description "RES SMD 22 OHM 1% 1/8W 0805")
      (fields
        (field (name "MANUFACTURER") "Yageo")
        (field (name "MANUFACTURER PART NUMBER") "RC0805FR-0722RL")
        (field (name ".CREATOR") "MM")
        (field (name ".CHECKED PCB") "RF")
        (field (name ".CHECKED SCH") "RF")
      )
      (libsource (lib "Integrated_Library_FEDEVEL_APR_2015") (part "RC0805FR-0722RL"))
    )
    (comp (ref "R24")
      (value "22R")
      (footprint "R0805")
      (description "RES SMD 22 OHM 1% 1/8W 0805")
      (fields
        (field (name "MANUFACTURER") "Yageo")
        (field (name "MANUFACTURER PART NUMBER") "RC0805FR-0722RL")
        (field (name ".CREATOR") "MM")
        (field (name ".CHECKED PCB") "RF")
        (field (name ".CHECKED SCH") "RF")
      )
      (libsource (lib "Integrated_Library_FEDEVEL_APR_2015") (part "RC0805FR-0722RL"))
    )
    (comp (ref "R25")
      (value "22R")
      (footprint "R0805")
      (description "RES SMD 22 OHM 1% 1/8W 0805")
      (fields
        (field (name "MANUFACTURER") "Yageo")
        (field (name "MANUFACTURER PART NUMBER") "RC0805FR-0722RL")
        (field (name ".CREATOR") "MM")
        (field (name ".CHECKED PCB") "RF")
        (field (name ".CHECKED SCH") "RF")
      )
      (libsource (lib "Integrated_Library_FEDEVEL_APR_2015") (part "RC0805FR-0722RL"))
    )
    (comp (ref "R26")
      (value "0R")
      (footprint "R0805")
      (description "RES 0.0 OHM 1/8W 0805 SMD")
      (fields
        (field (name "MANUFACTURER") "Yageo")
        (field (name "MANUFACTURER PART NUMBER") "RC0805JR-070RL")
        (field (name ".CHECKED PCB") "RF")
        (field (name ".CHECKED SCH") "RF")
      )
      (libsource (lib "Integrated_Library_FEDEVEL_APR_2015") (part "RC0805JR-070RL"))
    )
    (comp (ref "R27")
      (value "0R")
      (footprint "R0805")
      (description "RES 0.0 OHM 1/8W 0805 SMD")
      (fields
        (field (name "MANUFACTURER") "Yageo")
        (field (name "MANUFACTURER PART NUMBER") "RC0805JR-070RL")
        (field (name ".CHECKED PCB") "RF")
        (field (name ".CHECKED SCH") "RF")
      )
      (libsource (lib "Integrated_Library_FEDEVEL_APR_2015") (part "RC0805JR-070RL"))
    )
    (comp (ref "R28")
      (value "0R")
      (footprint "R0805")
      (description "RES 0.0 OHM 1/8W 0805 SMD")
      (fields
        (field (name "MANUFACTURER") "Yageo")
        (field (name "MANUFACTURER PART NUMBER") "RC0805JR-070RL")
        (field (name ".CHECKED PCB") "RF")
        (field (name ".CHECKED SCH") "RF")
      )
      (libsource (lib "Integrated_Library_FEDEVEL_APR_2015") (part "RC0805JR-070RL"))
    )
    (comp (ref "SCKT FOR U1")
      (value "28-DIP Socket")
      (footprint "28_DIP_7.62mm_SOCKET")
      (description "CONN IC DIP SOCKET 28POS TIN")
      (fields
        (field (name "MANUFACTURER") "3M")
        (field (name "MANUFACTURER PART NUMBER") "4828-3004-CP")
        (field (name ".CREATOR") "MM")
        (field (name ".CHECKED PCB") "RF")
        (field (name ".CHECKED SCH") "RF")
      )
      (libsource (lib "Integrated_Library_FEDEVEL_APR_2015") (part "4828-3004-CP"))
    )
    (comp (ref "SW1")
      (value "1825910-6")
      (footprint "1825910-6")
      (description "SWITCH TACTILE SPST-NO 0.05A 24V")
      (fields
        (field (name "MANUFACTURER") "TE Connectivity")
        (field (name ".CREATOR") "MM")
        (field (name ".CHECKED PCB") "RF")
        (field (name ".CHECKED SCH") "RF")
      )
      (libsource (lib "Integrated_Library_FEDEVEL_APR_2015") (part "1825910-6"))
    )
    (comp (ref "SW2")
      (value "1825910-6")
      (footprint "1825910-6")
      (description "SWITCH TACTILE SPST-NO 0.05A 24V")
      (fields
        (field (name "MANUFACTURER") "TE Connectivity")
        (field (name ".CREATOR") "MM")
        (field (name ".CHECKED PCB") "RF")
        (field (name ".CHECKED SCH") "RF")
      )
      (libsource (lib "Integrated_Library_FEDEVEL_APR_2015") (part "1825910-6"))
    )
    (comp (ref "U1")
      (value "ATMEGA328P-PU")
      (footprint "28_DIP_7.62mm")
      (description "IC MCU 8BIT 32KB FLASH 28DIP")
      (fields
        (field (name "MANUFACTURER") "Atmel")
        (field (name ".CREATOR") "MM")
        (field (name ".CHECKED PCB") "RF")
        (field (name ".CHECKED SCH") "RF")
      )
      (libsource (lib "Integrated_Library_FEDEVEL_APR_2015") (part "ATMEGA328P-PU"))
    )
    (comp (ref "U2")
      (value "ATMEGA16U2-AU")
      (footprint "TQFP32")
      (description "IC MCU 8BIT 16KB FLASH 32TQFP")
      (fields
        (field (name "MANUFACTURER") "Atmel")
        (field (name ".CREATOR") "MM")
        (field (name ".CHECKED PCB") "RF")
        (field (name ".CHECKED SCH") "RF")
      )
      (libsource (lib "Integrated_Library_FEDEVEL_APR_2015") (part "ATMEGA16U2-AU"))
    )
    (comp (ref "U3")
      (value "TL1963A-33DCQR")
      (footprint "DCQ (R-PDSO-G6)")
      (description "IC REG LDO 3.3V 1.5A SOT223-6")
      (fields
        (field (name "MANUFACTURER") "Texas Instruments")
        (field (name ".CREATOR") "MM")
        (field (name ".CHECKED PCB") "RF")
        (field (name ".CHECKED SCH") "RF")
      )
      (libsource (lib "Integrated_Library_FEDEVEL_APR_2015") (part "TL1963A-33DCQR"))
    )
    (comp (ref "U4")
      (value "SN74AHC1G09DBVR")
      (footprint "DBV_SOT_23_5")
      (description "IC GATE AND SGL 2INP SOT23-5")
      (fields (field (name "MANUFACTURER") "Texas Instruments") (field (name ".CREATOR") "MM"))
      (libsource (lib "Integrated_Library_FEDEVEL_APR_2015") (part "SN74AHC1G09DBVR"))
    )
    (comp (ref "U5")
      (value "SN74AHC1G09DBVR")
      (footprint "DBV_SOT_23_5")
      (description "IC GATE AND SGL 2INP SOT23-5")
      (fields (field (name "MANUFACTURER") "Texas Instruments") (field (name ".CREATOR") "MM"))
      (libsource (lib "Integrated_Library_FEDEVEL_APR_2015") (part "SN74AHC1G09DBVR"))
    )
    (comp (ref "U6")
      (value "SN74AHC1G09DBVR")
      (footprint "DBV_SOT_23_5")
      (description "IC GATE AND SGL 2INP SOT23-5")
      (fields (field (name "MANUFACTURER") "Texas Instruments") (field (name ".CREATOR") "MM"))
      (libsource (lib "Integrated_Library_FEDEVEL_APR_2015") (part "SN74AHC1G09DBVR"))
    )
    (comp (ref "U7")
      (value "SN74AHC1G09DBVR")
      (footprint "DBV_SOT_23_5")
      (description "IC GATE AND SGL 2INP SOT23-5")
      (fields (field (name "MANUFACTURER") "Texas Instruments") (field (name ".CREATOR") "MM"))
      (libsource (lib "Integrated_Library_FEDEVEL_APR_2015") (part "SN74AHC1G09DBVR"))
    )
    (comp (ref "Y1")
      (value "ABM7-16.000MHZ-D2Y-T")
      (footprint "ABM7_v1_1_BIG")
      (description "CRYSTAL 16MHZ 18PF SMD")
      (fields
        (field (name "MANUFACTURER") "Abracon LLC")
        (field (name ".CREATOR") "MM")
        (field (name ".CHECKED PCB") "RF")
        (field (name ".CHECKED SCH") "RF")
      )
      (libsource (lib "Integrated_Library_FEDEVEL_APR_2015") (part "ABM7-16.000MHZ-D2Y-T"))
    )
    (comp (ref "Y2")
      (value "ABM7-16.000MHZ-D2Y-T")
      (footprint "ABM7_v1_1_BIG")
      (description "CRYSTAL 16MHZ 18PF SMD")
      (fields
        (field (name "MANUFACTURER") "Abracon LLC")
        (field (name ".CREATOR") "MM")
        (field (name ".CHECKED PCB") "RF")
        (field (name ".CHECKED SCH") "RF")
      )
      (libsource (lib "Integrated_Library_FEDEVEL_APR_2015") (part "ABM7-16.000MHZ-D2Y-T"))
    )
    (comp (ref "Z1")
      (value "CG0603MLC-05E")
      (footprint "R0603")
      (description "VARISTOR 0603")
      (fields
        (field (name "MANUFACTURER") "Bourns Inc.")
        (field (name ".CREATOR") "MM")
        (field (name ".CHECKED PCB") "RF")
        (field (name ".CHECKED SCH") "RF")
      )
      (libsource (lib "Integrated_Library_FEDEVEL_APR_2015") (part "CG0603MLC-05E"))
    )
    (comp (ref "Z2")
      (value "CG0603MLC-05E")
      (footprint "R0603")
      (description "VARISTOR 0603")
      (fields
        (field (name "MANUFACTURER") "Bourns Inc.")
        (field (name ".CREATOR") "MM")
        (field (name ".CHECKED PCB") "RF")
        (field (name ".CHECKED SCH") "RF")
      )
      (libsource (lib "Integrated_Library_FEDEVEL_APR_2015") (part "CG0603MLC-05E"))
    )
  )
  (nets
    (net (code "1") (name "+3V3") (class "Default")
      (node (ref "C13") (pin "1") (pinfunction "1_1") (pintype "passive"))
      (node (ref "C16") (pin "1") (pinfunction "1_1") (pintype "passive"))
      (node (ref "J1") (pin "4") (pinfunction "4_4") (pintype "passive"))
      (node (ref "JP4") (pin "3") (pinfunction "3_3") (pintype "passive"))
      (node (ref "R28") (pin "1") (pinfunction "1_1") (pintype "passive"))
      (node (ref "U3") (pin "4") (pinfunction "OUT_4") (pintype "passive"))
      (node (ref "U3") (pin "5") (pinfunction "SENSE_5") (pintype "passive"))
    )
    (net (code "2") (name "+5V") (class "Default")
      (node (ref "C12") (pin "1") (pinfunction "1_1") (pintype "passive"))
      (node (ref "C14") (pin "1") (pinfunction "1_1") (pintype "passive"))
      (node (ref "C2") (pin "1") (pinfunction "1_1") (pintype "passive"))
      (node (ref "C6") (pin "1") (pinfunction "1_1") (pintype "passive"))
      (node (ref "J1") (pin "5") (pinfunction "5_5") (pintype "passive"))
      (node (ref "J8") (pin "1") (pinfunction "1_1") (pintype "passive"))
      (node (ref "JP4") (pin "1") (pinfunction "1_1") (pintype "passive"))
      (node (ref "L1") (pin "2") (pinfunction "2_2") (pintype "passive"))
      (node (ref "R27") (pin "2") (pinfunction "2_2") (pintype "passive"))
      (node (ref "U2") (pin "31") (pinfunction "UVCC_31") (pintype "passive"))
      (node (ref "U3") (pin "1") (pinfunction "~{SHDN}_1") (pintype "passive"))
      (node (ref "U3") (pin "2") (pinfunction "IN_2") (pintype "passive"))
    )
    (net (code "3") (name "+5V{slash}3V3") (class "Default")
      (node (ref "C15") (pin "1") (pinfunction "1_1") (pintype "passive"))
      (node (ref "C17") (pin "1") (pinfunction "1_1") (pintype "passive"))
      (node (ref "C26") (pin "1") (pinfunction "1_1") (pintype "passive"))
      (node (ref "C28") (pin "1") (pinfunction "1_1") (pintype "passive"))
      (node (ref "C29") (pin "1") (pinfunction "1_1") (pintype "passive"))
      (node (ref "C30") (pin "1") (pinfunction "1_1") (pintype "passive"))
      (node (ref "C34") (pin "1") (pinfunction "1_1") (pintype "passive"))
      (node (ref "C8") (pin "1") (pinfunction "1_1") (pintype "passive"))
      (node (ref "D5") (pin "1") (pinfunction "Cathode_1") (pintype "passive"))
      (node (ref "D6") (pin "1") (pinfunction "Cathode_1") (pintype "passive"))
      (node (ref "FB1") (pin "1") (pinfunction "1_1") (pintype "passive"))
      (node (ref "FB2") (pin "1") (pinfunction "1_1") (pintype "passive"))
      (node (ref "FB3") (pin "1") (pinfunction "1_1") (pintype "passive"))
      (node (ref "J1") (pin "2") (pinfunction "2_2") (pintype "passive"))
      (node (ref "J5") (pin "2") (pinfunction "2_2") (pintype "passive"))
      (node (ref "J6") (pin "2") (pinfunction "2_2") (pintype "passive"))
      (node (ref "JP4") (pin "2") (pinfunction "2_2") (pintype "passive"))
      (node (ref "R1") (pin "2") (pinfunction "2_2") (pintype "passive"))
      (node (ref "R14") (pin "2") (pinfunction "2_2") (pintype "passive"))
      (node (ref "R15") (pin "2") (pinfunction "2_2") (pintype "passive"))
      (node (ref "R17") (pin "2") (pinfunction "2_2") (pintype "passive"))
      (node (ref "R18") (pin "2") (pinfunction "2_2") (pintype "passive"))
      (node (ref "R19") (pin "2") (pinfunction "2_2") (pintype "passive"))
      (node (ref "R2") (pin "2") (pinfunction "2_2") (pintype "passive"))
      (node (ref "R20") (pin "2") (pinfunction "2_2") (pintype "passive"))
      (node (ref "R21") (pin "2") (pinfunction "2_2") (pintype "passive"))
      (node (ref "R27") (pin "1") (pinfunction "1_1") (pintype "passive"))
      (node (ref "R28") (pin "2") (pinfunction "2_2") (pintype "passive"))
      (node (ref "R3") (pin "2") (pinfunction "2_2") (pintype "passive"))
      (node (ref "R4") (pin "2") (pinfunction "2_2") (pintype "passive"))
      (node (ref "U4") (pin "5") (pinfunction "VCC_5") (pintype "power_in"))
      (node (ref "U5") (pin "5") (pinfunction "VCC_5") (pintype "power_in"))
      (node (ref "U6") (pin "5") (pinfunction "VCC_5") (pintype "power_in"))
      (node (ref "U7") (pin "5") (pinfunction "VCC_5") (pintype "power_in"))
    )
    (net (code "4") (name "+AREF") (class "Default")
      (node (ref "C21") (pin "1") (pinfunction "1_1") (pintype "passive"))
      (node (ref "C24") (pin "1") (pinfunction "1_1") (pintype "passive"))
      (node (ref "J4") (pin "8") (pinfunction "8_8") (pintype "passive"))
      (node (ref "U1") (pin "21") (pinfunction "AREF_21") (pintype "passive"))
    )
    (net (code "5") (name "/+3V3_16U2_UCAP") (class "Default")
      (node (ref "C7") (pin "2") (pinfunction "2_2") (pintype "passive"))
      (node (ref "R26") (pin "1") (pinfunction "1_1") (pintype "passive"))
      (node (ref "U2") (pin "27") (pinfunction "UCAP_27") (pintype "passive"))
    )
    (net (code "6") (name "/+5V_USB") (class "Default")
      (node (ref "C1") (pin "1") (pinfunction "1_1") (pintype "passive"))
      (node (ref "J7") (pin "1") (pinfunction "P1_1") (pintype "passive"))
      (node (ref "L1") (pin "1") (pinfunction "1_1") (pintype "passive"))
    )
    (net (code "7") (name "/+5V{slash}3V3_16U2") (class "Default")
      (node (ref "C5") (pin "1") (pinfunction "1_1") (pintype "passive"))
      (node (ref "FB1") (pin "2") (pinfunction "2_2") (pintype "passive"))
      (node (ref "R26") (pin "2") (pinfunction "2_2") (pintype "passive"))
      (node (ref "U2") (pin "32") (pinfunction "AVCC_32") (pintype "passive"))
      (node (ref "U2") (pin "4") (pinfunction "VCC_4") (pintype "passive"))
    )
    (net (code "8") (name "/+5V{slash}3V3_328P_AVCC") (class "Default")
      (node (ref "C22") (pin "1") (pinfunction "1_1") (pintype "passive"))
      (node (ref "C23") (pin "1") (pinfunction "1_1") (pintype "passive"))
      (node (ref "FB3") (pin "2") (pinfunction "2_2") (pintype "passive"))
      (node (ref "U1") (pin "20") (pinfunction "AVCC_20") (pintype "passive"))
    )
    (net (code "9") (name "/+5V{slash}3V3_328P_VCC") (class "Default")
      (node (ref "C19") (pin "1") (pinfunction "1_1") (pintype "passive"))
      (node (ref "C20") (pin "1") (pinfunction "1_1") (pintype "passive"))
      (node (ref "FB2") (pin "2") (pinfunction "2_2") (pintype "passive"))
      (node (ref "U1") (pin "7") (pinfunction "VCC_7") (pintype "passive"))
    )
    (net (code "10") (name "/16U2PROG_328P_RESETn") (class "Default")
      (node (ref "JP1") (pin "2") (pinfunction "2_2") (pintype "passive"))
      (node (ref "R1") (pin "1") (pinfunction "1_1") (pintype "passive"))
      (node (ref "U2") (pin "13") (pinfunction "~{CTS}_/~{_HWB}_/_T0_/_AIN6_/_INT7_/_PD7_13") (pintype "passive"))
    )
    (net (code "11") (name "/16U2_16MHZ_XTAL1") (class "Default")
      (node (ref "C10") (pin "2") (pinfunction "2_2") (pintype "passive"))
      (node (ref "R9") (pin "1") (pinfunction "1_1") (pintype "passive"))
      (node (ref "U2") (pin "1") (pinfunction "XTAL1_1") (pintype "passive"))
      (node (ref "Y2") (pin "1") (pinfunction "1_1") (pintype "passive"))
    )
    (net (code "12") (name "/16U2_16MHZ_XTAL2") (class "Default")
      (node (ref "C9") (pin "2") (pinfunction "2_2") (pintype "passive"))
      (node (ref "R9") (pin "2") (pinfunction "2_2") (pintype "passive"))
      (node (ref "U2") (pin "2") (pinfunction "XTAL2_/_PC0_2") (pintype "passive"))
      (node (ref "Y2") (pin "2") (pinfunction "2_2") (pintype "passive"))
    )
    (net (code "13") (name "/16U2_BUF_RESETn") (class "Default")
      (node (ref "C31") (pin "1") (pinfunction "1_1") (pintype "passive"))
      (node (ref "R23") (pin "2") (pinfunction "2_2") (pintype "passive"))
      (node (ref "U5") (pin "1") (pinfunction "A_1") (pintype "passive"))
      (node (ref "U5") (pin "2") (pinfunction "B_2") (pintype "passive"))
    )
    (net (code "14") (name "/16U2_HDR_RESETn") (class "Default")
      (node (ref "J6") (pin "5") (pinfunction "5_5") (pintype "passive"))
      (node (ref "JP3") (pin "3") (pinfunction "3_3") (pintype "passive"))
    )
    (net (code "15") (name "/16U2_MISO") (class "Default")
      (node (ref "J6") (pin "1") (pinfunction "1_1") (pintype "passive"))
      (node (ref "U2") (pin "17") (pinfunction "PDO_/_MISO_/_PCINT3_/_PB3_17") (pintype "passive"))
    )
    (net (code "16") (name "/16U2_MOSI") (class "Default")
      (node (ref "J6") (pin "4") (pinfunction "4_4") (pintype "passive"))
      (node (ref "U2") (pin "16") (pinfunction "PDI_/_MOSI_/_PCINT2_/_PB2_16") (pintype "passive"))
    )
    (net (code "17") (name "/16U2_PB4") (class "Default")
      (node (ref "JP2") (pin "1") (pinfunction "1_1") (pintype "passive"))
      (node (ref "JP3") (pin "2") (pinfunction "2_2") (pintype "passive"))
      (node (ref "U2") (pin "18") (pinfunction "T1_/_PCINT4_/_PB4_18") (pintype "passive"))
    )
    (net (code "18") (name "/16U2_PB5") (class "Default")
      (node (ref "JP2") (pin "3") (pinfunction "3_3") (pintype "passive"))
      (node (ref "U2") (pin "19") (pinfunction "PCINT5_/_PB5_19") (pintype "passive"))
    )
    (net (code "19") (name "/16U2_PB6") (class "Default")
      (node (ref "JP2") (pin "2") (pinfunction "2_2") (pintype "passive"))
      (node (ref "U2") (pin "20") (pinfunction "PCINT6_/_PB6_20") (pintype "passive"))
    )
    (net (code "20") (name "/16U2_PB7") (class "Default")
      (node (ref "JP2") (pin "4") (pinfunction "4_4") (pintype "passive"))
      (node (ref "U2") (pin "21") (pinfunction "OC.0A_/_OC.1C_/_PCINT7_/_PB7_21") (pintype "passive"))
    )
    (net (code "21") (name "/16U2_RESETn") (class "Default")
      (node (ref "JP3") (pin "4") (pinfunction "4_4") (pintype "passive"))
      (node (ref "R4") (pin "1") (pinfunction "1_1") (pintype "passive"))
      (node (ref "U2") (pin "24") (pinfunction "PC1_/~{_RESET}_/_DW_24") (pintype "passive"))
      (node (ref "U5") (pin "4") (pinfunction "Y_4") (pintype "passive"))
    )
    (net (code "22") (name "/16U2_RXD") (class "Default")
      (node (ref "R11") (pin "1") (pinfunction "1_1") (pintype "passive"))
      (node (ref "U2") (pin "8") (pinfunction "RXD1_/_AIN1_/_INT2_/_PD2_8") (pintype "passive"))
    )
    (net (code "23") (name "/16U2_RX_LED") (class "Default")
      (node (ref "D4") (pin "1") (pinfunction "cathode_1") (pintype "passive"))
      (node (ref "U2") (pin "10") (pinfunction "AIN3_/_INT5_/_PD4_10") (pintype "passive"))
    )
    (net (code "24") (name "/16U2_SCLK") (class "Default")
      (node (ref "J6") (pin "3") (pinfunction "3_3") (pintype "passive"))
      (node (ref "R5") (pin "2") (pinfunction "2_2") (pintype "passive"))
    )
    (net (code "25") (name "/16U2_SCLK_R") (class "Default")
      (node (ref "R5") (pin "1") (pinfunction "1_1") (pintype "passive"))
      (node (ref "U2") (pin "15") (pinfunction "SCLK_/_PCINT1_/_PB1_15") (pintype "passive"))
    )
    (net (code "26") (name "/16U2_TXD") (class "Default")
      (node (ref "R10") (pin "1") (pinfunction "1_1") (pintype "passive"))
      (node (ref "U2") (pin "9") (pinfunction "TXD1_/_INT3_/_PD3_9") (pintype "passive"))
    )
    (net (code "27") (name "/16U2_TX_LED") (class "Default")
      (node (ref "D3") (pin "1") (pinfunction "cathode_1") (pintype "passive"))
      (node (ref "U2") (pin "11") (pinfunction "XCK_/_AIN4_/_PCINT12_/_PD5_11") (pintype "passive"))
    )
    (net (code "28") (name "/328P_16MHZ_XTAL1") (class "Default")
      (node (ref "C27") (pin "2") (pinfunction "2_2") (pintype "passive"))
      (node (ref "R16") (pin "1") (pinfunction "1_1") (pintype "passive"))
      (node (ref "U1") (pin "9") (pinfunction "PB6_/_PCINT6_/_TOSC1_/_XTAL1_9") (pintype "passive"))
      (node (ref "Y1") (pin "1") (pinfunction "1_1") (pintype "passive"))
    )
    (net (code "29") (name "/328P_16MHZ_XTAL2") (class "Default")
      (node (ref "C25") (pin "2") (pinfunction "2_2") (pintype "passive"))
      (node (ref "R16") (pin "2") (pinfunction "2_2") (pintype "passive"))
      (node (ref "U1") (pin "10") (pinfunction "PB7_/_PCINT7_/_TOSC2_/_XTAL2_10") (pintype "passive"))
      (node (ref "Y1") (pin "2") (pinfunction "2_2") (pintype "passive"))
    )
    (net (code "30") (name "/328P_AUTORESETn") (class "Default")
      (node (ref "C11") (pin "1") (pinfunction "1_1") (pintype "passive"))
      (node (ref "R18") (pin "1") (pinfunction "1_1") (pintype "passive"))
      (node (ref "U6") (pin "1") (pinfunction "A_1") (pintype "passive"))
    )
    (net (code "31") (name "/328P_BUF_RESETn") (class "Default")
      (node (ref "C32") (pin "1") (pinfunction "1_1") (pintype "passive"))
      (node (ref "R24") (pin "2") (pinfunction "2_2") (pintype "passive"))
      (node (ref "U6") (pin "2") (pinfunction "B_2") (pintype "passive"))
    )
    (net (code "32") (name "/328P_RESETn") (class "Default")
      (node (ref "J1") (pin "3") (pinfunction "3_3") (pintype "passive"))
      (node (ref "J5") (pin "5") (pinfunction "5_5") (pintype "passive"))
      (node (ref "JP3") (pin "1") (pinfunction "1_1") (pintype "passive"))
      (node (ref "R14") (pin "1") (pinfunction "1_1") (pintype "passive"))
      (node (ref "U1") (pin "1") (pinfunction "PC6_/_PCINT14_/~{_RESET}_1") (pintype "passive"))
      (node (ref "U6") (pin "4") (pinfunction "Y_4") (pintype "passive"))
    )
    (net (code "33") (name "/AD0") (class "Default")
      (node (ref "J2") (pin "1") (pinfunction "1_1") (pintype "passive"))
      (node (ref "U1") (pin "23") (pinfunction "PCINT8_/_ADC0_/_PC0_23") (pintype "passive"))
    )
    (net (code "34") (name "/AD1") (class "Default")
      (node (ref "J2") (pin "2") (pinfunction "2_2") (pintype "passive"))
      (node (ref "U1") (pin "24") (pinfunction "PCINT9_/_ADC1_/_PC1_24") (pintype "passive"))
    )
    (net (code "35") (name "/AD2") (class "Default")
      (node (ref "J2") (pin "3") (pinfunction "3_3") (pintype "passive"))
      (node (ref "U1") (pin "25") (pinfunction "PCINT10_/_ADC2_/_PC2_25") (pintype "passive"))
    )
    (net (code "36") (name "/AD3") (class "Default")
      (node (ref "J2") (pin "4") (pinfunction "4_4") (pintype "passive"))
      (node (ref "U1") (pin "26") (pinfunction "PCINT11_/_ADC3_/_PC3_26") (pintype "passive"))
    )
    (net (code "37") (name "/AD4{slash}SDA") (class "Default")
      (node (ref "J2") (pin "5") (pinfunction "5_5") (pintype "passive"))
      (node (ref "J4") (pin "9") (pinfunction "9_9") (pintype "passive"))
      (node (ref "U1") (pin "27") (pinfunction "SDA_/_PCINT12_/_ADC4_/_PC4_27") (pintype "passive"))
    )
    (net (code "38") (name "/AD5{slash}SCL") (class "Default")
      (node (ref "J2") (pin "6") (pinfunction "6_6") (pintype "passive"))
      (node (ref "J4") (pin "10") (pinfunction "10_10") (pintype "passive"))
      (node (ref "U1") (pin "28") (pinfunction "SCL_/_PCINT13_/_ADC5_/_PC5_28") (pintype "passive"))
    )
    (net (code "39") (name "/BUTTON_RESETn") (class "Default")
      (node (ref "D6") (pin "2") (pinfunction "Anode_2") (pintype "passive"))
      (node (ref "R20") (pin "1") (pinfunction "1_1") (pintype "passive"))
      (node (ref "R24") (pin "1") (pinfunction "1_1") (pintype "passive"))
      (node (ref "SW1") (pin "1") (pinfunction "1_1") (pintype "passive"))
      (node (ref "SW1") (pin "2") (pinfunction "2_2") (pintype "passive"))
    )
    (net (code "40") (name "/CON_USB_N") (class "Default")
      (node (ref "J7") (pin "2") (pinfunction "P2_2") (pintype "passive"))
      (node (ref "R6") (pin "1") (pinfunction "1_1") (pintype "passive"))
      (node (ref "Z1") (pin "2") (pinfunction "2_2") (pintype "passive"))
    )
    (net (code "41") (name "/CON_USB_P") (class "Default")
      (node (ref "J7") (pin "3") (pinfunction "P3_3") (pintype "passive"))
      (node (ref "R7") (pin "1") (pinfunction "1_1") (pintype "passive"))
      (node (ref "Z2") (pin "2") (pinfunction "2_2") (pintype "passive"))
    )
    (net (code "42") (name "/IO0") (class "Default")
      (node (ref "J3") (pin "1") (pinfunction "1_1") (pintype "passive"))
      (node (ref "R10") (pin "2") (pinfunction "2_2") (pintype "passive"))
      (node (ref "U1") (pin "2") (pinfunction "RXD_/_PCINT16_/_PD0_2") (pintype "passive"))
    )
    (net (code "43") (name "/IO1") (class "Default")
      (node (ref "J3") (pin "2") (pinfunction "2_2") (pintype "passive"))
      (node (ref "R11") (pin "2") (pinfunction "2_2") (pintype "passive"))
      (node (ref "U1") (pin "3") (pinfunction "TXD_/_PCINT17_/_PD1_3") (pintype "passive"))
    )
    (net (code "44") (name "/IO2") (class "Default")
      (node (ref "J3") (pin "3") (pinfunction "3_3") (pintype "passive"))
      (node (ref "U1") (pin "4") (pinfunction "INT0_/_PCINT18_/_PD2_4") (pintype "passive"))
    )
    (net (code "45") (name "/IO3") (class "Default")
      (node (ref "J3") (pin "4") (pinfunction "4_4") (pintype "passive"))
      (node (ref "U1") (pin "5") (pinfunction "OC2B_/_INT1_/_PCINT19_/_PD3_5") (pintype "passive"))
    )
    (net (code "46") (name "/IO4") (class "Default")
      (node (ref "J3") (pin "5") (pinfunction "5_5") (pintype "passive"))
      (node (ref "U1") (pin "6") (pinfunction "XCK_/_T0_/_PCINT20_/_PD4_6") (pintype "passive"))
    )
    (net (code "47") (name "/IO5") (class "Default")
      (node (ref "J3") (pin "6") (pinfunction "6_6") (pintype "passive"))
      (node (ref "U1") (pin "11") (pinfunction "OC0B_/_T1_/_PCINT21_/_PD5_11") (pintype "passive"))
    )
    (net (code "48") (name "/IO6") (class "Default")
      (node (ref "J3") (pin "7") (pinfunction "7_7") (pintype "passive"))
      (node (ref "U1") (pin "12") (pinfunction "OC0A_/_AIN0_/_PCINT22_/_PD6_12") (pintype "passive"))
    )
    (net (code "49") (name "/IO7") (class "Default")
      (node (ref "J3") (pin "8") (pinfunction "8_8") (pintype "passive"))
      (node (ref "U1") (pin "13") (pinfunction "AIN1_/_PCINT23_/_PD7_13") (pintype "passive"))
    )
    (net (code "50") (name "/IO8") (class "Default")
      (node (ref "J4") (pin "1") (pinfunction "1_1") (pintype "passive"))
      (node (ref "R22") (pin "1") (pinfunction "1_1") (pintype "passive"))
      (node (ref "U1") (pin "14") (pinfunction "CLKO_/_ICP1_/_PCINT0_/_PB0_14") (pintype "passive"))
    )
    (net (code "51") (name "/IO9") (class "Default")
      (node (ref "J4") (pin "2") (pinfunction "2_2") (pintype "passive"))
      (node (ref "U1") (pin "15") (pinfunction "OC1A_/_PCINT1_/_PB1_15") (pintype "passive"))
    )
    (net (code "52") (name "/MISO") (class "Default")
      (node (ref "J4") (pin "5") (pinfunction "5_5") (pintype "passive"))
      (node (ref "J5") (pin "1") (pinfunction "1_1") (pintype "passive"))
      (node (ref "U1") (pin "18") (pinfunction "MISO_/_PCINT4_/_PB4_18") (pintype "passive"))
    )
    (net (code "53") (name "/MOSI") (class "Default")
      (node (ref "J4") (pin "4") (pinfunction "4_4") (pintype "passive"))
      (node (ref "J5") (pin "4") (pinfunction "4_4") (pintype "passive"))
      (node (ref "U1") (pin "17") (pinfunction "MOSI_/_OC2A_/_PCINT3_/_PB3_17") (pintype "passive"))
    )
    (net (code "54") (name "/SCK") (class "Default")
      (node (ref "J4") (pin "6") (pinfunction "6_6") (pintype "passive"))
      (node (ref "J5") (pin "3") (pinfunction "3_3") (pintype "passive"))
      (node (ref "R13") (pin "2") (pinfunction "2_2") (pintype "passive"))
      (node (ref "U4") (pin "1") (pinfunction "A_1") (pintype "passive"))
      (node (ref "U4") (pin "2") (pinfunction "B_2") (pintype "passive"))
    )
    (net (code "55") (name "/SCK_R") (class "Default")
      (node (ref "R13") (pin "1") (pinfunction "1_1") (pintype "passive"))
      (node (ref "U1") (pin "19") (pinfunction "SCK_/_PCINT5_/_PB5_19") (pintype "passive"))
    )
    (net (code "56") (name "/SS") (class "Default")
      (node (ref "J4") (pin "3") (pinfunction "3_3") (pintype "passive"))
      (node (ref "U1") (pin "16") (pinfunction "~{SS}_/_OC1B_/_PCINT2_/_PB2_16") (pintype "passive"))
    )
    (net (code "57") (name "/USB_N") (class "Default")
      (node (ref "R6") (pin "2") (pinfunction "2_2") (pintype "passive"))
      (node (ref "U2") (pin "30") (pinfunction "D-_30") (pintype "passive"))
    )
    (net (code "58") (name "/USB_P") (class "Default")
      (node (ref "R7") (pin "2") (pinfunction "2_2") (pintype "passive"))
      (node (ref "U2") (pin "29") (pinfunction "D+_29") (pintype "passive"))
    )
    (net (code "59") (name "/USER_BUTTON") (class "Default")
      (node (ref "R21") (pin "1") (pinfunction "1_1") (pintype "passive"))
      (node (ref "R25") (pin "1") (pinfunction "1_1") (pintype "passive"))
      (node (ref "SW2") (pin "1") (pinfunction "1_1") (pintype "passive"))
      (node (ref "SW2") (pin "2") (pinfunction "2_2") (pintype "passive"))
    )
    (net (code "60") (name "/USER_BUTTON_BUF") (class "Default")
      (node (ref "C33") (pin "1") (pinfunction "1_1") (pintype "passive"))
      (node (ref "R25") (pin "2") (pinfunction "2_2") (pintype "passive"))
      (node (ref "U7") (pin "1") (pinfunction "A_1") (pintype "passive"))
      (node (ref "U7") (pin "2") (pinfunction "B_2") (pintype "passive"))
    )
    (net (code "61") (name "GND") (class "Default")
      (node (ref "C1") (pin "2") (pinfunction "2_2") (pintype "passive"))
      (node (ref "C10") (pin "1") (pinfunction "1_1") (pintype "passive"))
      (node (ref "C12") (pin "2") (pinfunction "2_2") (pintype "passive"))
      (node (ref "C13") (pin "2") (pinfunction "2_2") (pintype "passive"))
      (node (ref "C14") (pin "2") (pinfunction "2_2") (pintype "passive"))
      (node (ref "C15") (pin "2") (pinfunction "2_2") (pintype "passive"))
      (node (ref "C16") (pin "2") (pinfunction "2_2") (pintype "passive"))
      (node (ref "C17") (pin "2") (pinfunction "2_2") (pintype "passive"))
      (node (ref "C19") (pin "2") (pinfunction "2_2") (pintype "passive"))
      (node (ref "C2") (pin "2") (pinfunction "2_2") (pintype "passive"))
      (node (ref "C20") (pin "2") (pinfunction "2_2") (pintype "passive"))
      (node (ref "C21") (pin "2") (pinfunction "2_2") (pintype "passive"))
      (node (ref "C22") (pin "2") (pinfunction "2_2") (pintype "passive"))
      (node (ref "C23") (pin "2") (pinfunction "2_2") (pintype "passive"))
      (node (ref "C24") (pin "2") (pinfunction "2_2") (pintype "passive"))
      (node (ref "C25") (pin "1") (pinfunction "1_1") (pintype "passive"))
      (node (ref "C26") (pin "2") (pinfunction "2_2") (pintype "passive"))
      (node (ref "C27") (pin "1") (pinfunction "1_1") (pintype "passive"))
      (node (ref "C28") (pin "2") (pinfunction "2_2") (pintype "passive"))
      (node (ref "C29") (pin "2") (pinfunction "2_2") (pintype "passive"))
      (node (ref "C30") (pin "2") (pinfunction "2_2") (pintype "passive"))
      (node (ref "C31") (pin "2") (pinfunction "2_2") (pintype "passive"))
      (node (ref "C32") (pin "2") (pinfunction "2_2") (pintype "passive"))
      (node (ref "C33") (pin "2") (pinfunction "2_2") (pintype "passive"))
      (node (ref "C34") (pin "2") (pinfunction "2_2") (pintype "passive"))
      (node (ref "C5") (pin "2") (pinfunction "2_2") (pintype "passive"))
      (node (ref "C6") (pin "2") (pinfunction "2_2") (pintype "passive"))
      (node (ref "C7") (pin "1") (pinfunction "1_1") (pintype "passive"))
      (node (ref "C8") (pin "2") (pinfunction "2_2") (pintype "passive"))
      (node (ref "C9") (pin "1") (pinfunction "1_1") (pintype "passive"))
      (node (ref "D1") (pin "1") (pinfunction "cathode_1") (pintype "passive"))
      (node (ref "J1") (pin "6") (pinfunction "6_6") (pintype "passive"))
      (node (ref "J1") (pin "7") (pinfunction "7_7") (pintype "passive"))
      (node (ref "J4") (pin "7") (pinfunction "7_7") (pintype "passive"))
      (node (ref "J5") (pin "6") (pinfunction "6_6") (pintype "passive"))
      (node (ref "J6") (pin "6") (pinfunction "6_6") (pintype "passive"))
      (node (ref "J7") (pin "10") (pinfunction "10_10") (pintype "passive"))
      (node (ref "J7") (pin "11") (pinfunction "11_11") (pintype "passive"))
      (node (ref "J7") (pin "5") (pinfunction "P5_5") (pintype "passive"))
      (node (ref "J7") (pin "6") (pinfunction "6_6") (pintype "passive"))
      (node (ref "J7") (pin "7") (pinfunction "7_7") (pintype "passive"))
      (node (ref "J7") (pin "8") (pinfunction "8_8") (pintype "passive"))
      (node (ref "J7") (pin "9") (pinfunction "9_9") (pintype "passive"))
      (node (ref "J9") (pin "1") (pinfunction "1_1") (pintype "passive"))
      (node (ref "MH1") (pin "1") (pinfunction "1_1") (pintype "passive"))
      (node (ref "MH2") (pin "1") (pinfunction "1_1") (pintype "passive"))
      (node (ref "MH3") (pin "1") (pinfunction "1_1") (pintype "passive"))
      (node (ref "R12") (pin "2") (pinfunction "2_2") (pintype "passive"))
      (node (ref "R8") (pin "2") (pinfunction "2_2") (pintype "passive"))
      (node (ref "SW1") (pin "3") (pinfunction "MECH1_3") (pintype "passive"))
      (node (ref "SW1") (pin "4") (pinfunction "MECH2_4") (pintype "passive"))
      (node (ref "SW2") (pin "3") (pinfunction "MECH1_3") (pintype "passive"))
      (node (ref "SW2") (pin "4") (pinfunction "MECH2_4") (pintype "passive"))
      (node (ref "U1") (pin "22") (pinfunction "GND_2_22") (pintype "passive"))
      (node (ref "U1") (pin "8") (pinfunction "GND_1_8") (pintype "passive"))
      (node (ref "U2") (pin "28") (pinfunction "UGND_28") (pintype "passive"))
      (node (ref "U2") (pin "3") (pinfunction "GND_3") (pintype "passive"))
      (node (ref "U3") (pin "3") (pinfunction "GND_3") (pintype "passive"))
      (node (ref "U3") (pin "6") (pinfunction "EPAD_6") (pintype "passive"))
      (node (ref "U4") (pin "3") (pinfunction "GND_3") (pintype "power_in"))
      (node (ref "U5") (pin "3") (pinfunction "GND_3") (pintype "power_in"))
      (node (ref "U6") (pin "3") (pinfunction "GND_3") (pintype "power_in"))
      (node (ref "U7") (pin "3") (pinfunction "GND_3") (pintype "power_in"))
      (node (ref "Z1") (pin "1") (pinfunction "1_1") (pintype "passive"))
      (node (ref "Z2") (pin "1") (pinfunction "1_1") (pintype "passive"))
    )
    (net (code "62") (name "Net-(C11-Pad2)") (class "Default")
      (node (ref "C11") (pin "2") (pinfunction "2_2") (pintype "passive"))
      (node (ref "JP1") (pin "1") (pinfunction "1_1") (pintype "passive"))
    )
    (net (code "63") (name "Net-(D1-ANODE)") (class "Default")
      (node (ref "D1") (pin "2") (pinfunction "ANODE_2") (pintype "passive"))
      (node (ref "R17") (pin "1") (pinfunction "1_1") (pintype "passive"))
    )
    (net (code "64") (name "Net-(D2-ANODE)") (class "Default")
      (node (ref "D2") (pin "2") (pinfunction "ANODE_2") (pintype "passive"))
      (node (ref "R15") (pin "1") (pinfunction "1_1") (pintype "passive"))
    )
    (net (code "65") (name "Net-(D2-cathode)") (class "Default")
      (node (ref "D2") (pin "1") (pinfunction "cathode_1") (pintype "passive"))
      (node (ref "U4") (pin "4") (pinfunction "Y_4") (pintype "passive"))
    )
    (net (code "66") (name "Net-(D3-ANODE)") (class "Default")
      (node (ref "D3") (pin "2") (pinfunction "ANODE_2") (pintype "passive"))
      (node (ref "R2") (pin "1") (pinfunction "1_1") (pintype "passive"))
    )
    (net (code "67") (name "Net-(D4-ANODE)") (class "Default")
      (node (ref "D4") (pin "2") (pinfunction "ANODE_2") (pintype "passive"))
      (node (ref "R3") (pin "1") (pinfunction "1_1") (pintype "passive"))
    )
    (net (code "68") (name "Net-(D5-Anode)") (class "Default")
      (node (ref "D5") (pin "2") (pinfunction "Anode_2") (pintype "passive"))
      (node (ref "R19") (pin "1") (pinfunction "1_1") (pintype "passive"))
      (node (ref "R23") (pin "1") (pinfunction "1_1") (pintype "passive"))
    )
    (net (code "69") (name "Net-(J7-P4)") (class "Default")
      (node (ref "J7") (pin "4") (pinfunction "P4_4") (pintype "passive"))
      (node (ref "R8") (pin "1") (pinfunction "1_1") (pintype "passive"))
    )
    (net (code "70") (name "Net-(JP1-Pad3)") (class "Default")
      (node (ref "JP1") (pin "3") (pinfunction "3_3") (pintype "passive"))
      (node (ref "R12") (pin "1") (pinfunction "1_1") (pintype "passive"))
    )
    (net (code "71") (name "Net-(U7-Y)") (class "Default")
      (node (ref "R22") (pin "2") (pinfunction "2_2") (pintype "passive"))
      (node (ref "U7") (pin "4") (pinfunction "Y_4") (pintype "passive"))
    )
    (net (code "72") (name "unconnected-(J1-Pad1)") (class "Default")
      (node (ref "J1") (pin "1") (pinfunction "1_1") (pintype "passive+no_connect"))
    )
    (net (code "73") (name "unconnected-(J1-Pad8)") (class "Default")
      (node (ref "J1") (pin "8") (pinfunction "8_8") (pintype "passive+no_connect"))
    )
    (net (code "74") (name "unconnected-(MH4-Pad1)") (class "Default")
      (node (ref "MH4") (pin "1") (pinfunction "1_1") (pintype "passive+no_connect"))
    )
    (net (code "75") (name "unconnected-(U2-AIN0_{slash}_INT1_{slash}_PD1-Pad7)") (class "Default")
      (node (ref "U2") (pin "7") (pinfunction "AIN0_/_INT1_/_PD1_7") (pintype "passive+no_connect"))
    )
    (net (code "76") (name "unconnected-(U2-AIN2_{slash}_PCINT11_{slash}_PC2-Pad5)") (class "Default")
      (node (ref "U2") (pin "5") (pinfunction "AIN2_/_PCINT11_/_PC2_5") (pintype "passive+no_connect"))
    )
    (net (code "77") (name "unconnected-(U2-CLKO_{slash}_ICP1_{slash}_INT4_{slash}_PC7-Pad22)") (class "Default")
      (node (ref "U2") (pin "22") (pinfunction "CLKO_/_ICP1_/_INT4_/_PC7_22") (pintype "passive+no_connect"))
    )
    (net (code "78") (name "unconnected-(U2-OC.0B_{slash}_INT0_{slash}_PD0-Pad6)") (class "Default")
      (node (ref "U2") (pin "6") (pinfunction "OC.0B_/_INT0_/_PD0_6") (pintype "passive+no_connect"))
    )
    (net (code "79") (name "unconnected-(U2-OC.1A_{slash}_PCINT8_{slash}_PC6-Pad23)") (class "Default")
      (node (ref "U2") (pin "23") (pinfunction "OC.1A_/_PCINT8_/_PC6_23") (pintype "passive+no_connect"))
    )
    (net (code "80") (name "unconnected-(U2-OC.1B_{slash}_PCINT9_{slash}_PC5-Pad25)") (class "Default")
      (node (ref "U2") (pin "25") (pinfunction "OC.1B_/_PCINT9_/_PC5_25") (pintype "passive+no_connect"))
    )
    (net (code "81") (name "unconnected-(U2-PCINT10_{slash}_PC4-Pad26)") (class "Default")
      (node (ref "U2") (pin "26") (pinfunction "PCINT10_/_PC4_26") (pintype "passive+no_connect"))
    )
    (net (code "82") (name "unconnected-(U2-~{RTS}_{slash}_AIN5_{slash}_INT6_{slash}_PD6-Pad12)") (class "Default")
      (node (ref "U2") (pin "12") (pinfunction "~{RTS}_/_AIN5_/_INT6_/_PD6_12") (pintype "passive"))
    )
    (net (code "83") (name "unconnected-(U2-~{SS}_{slash}_PCINT0_{slash}_PB0-Pad14)") (class "Default")
      (node (ref "U2") (pin "14") (pinfunction "~{SS}_/_PCINT0_/_PB0_14") (pintype "passive+no_connect"))
    )
  )
)
